# Backlit-PCB-Art-Lamp.net
KiCad netlist of a schematic drawn in EasyEDA Pro
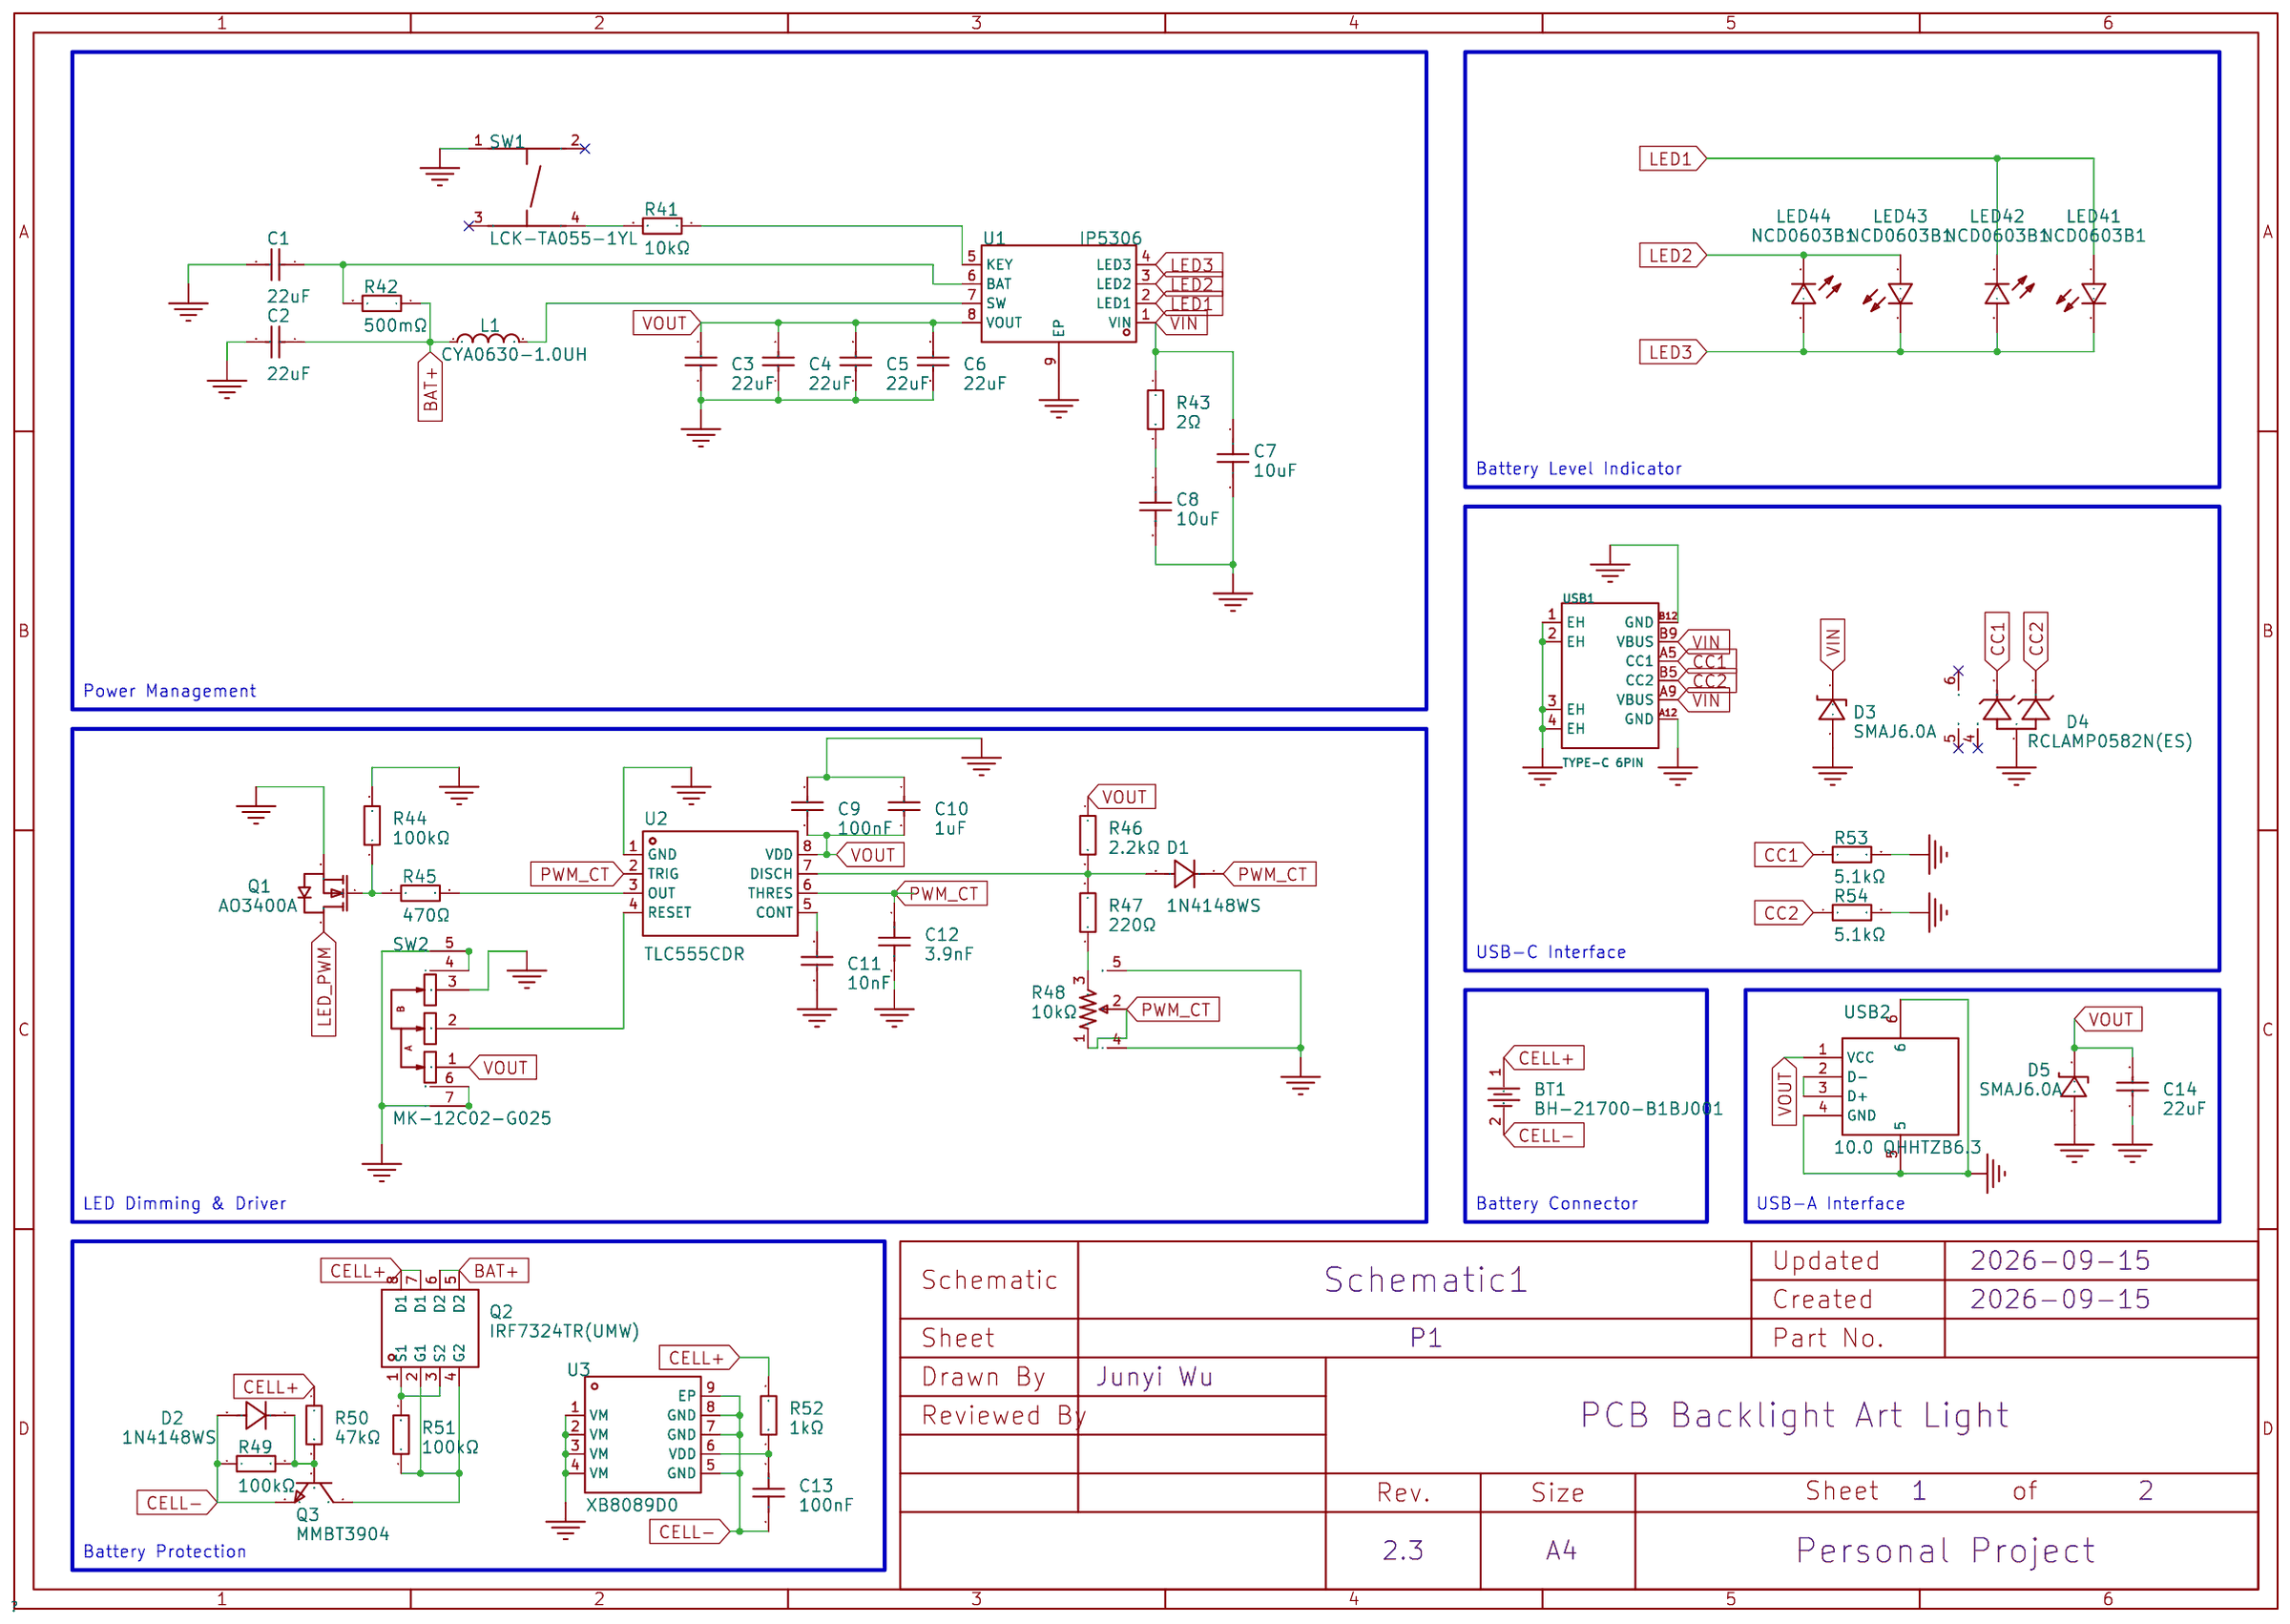
[diagram p0: Power & Control]
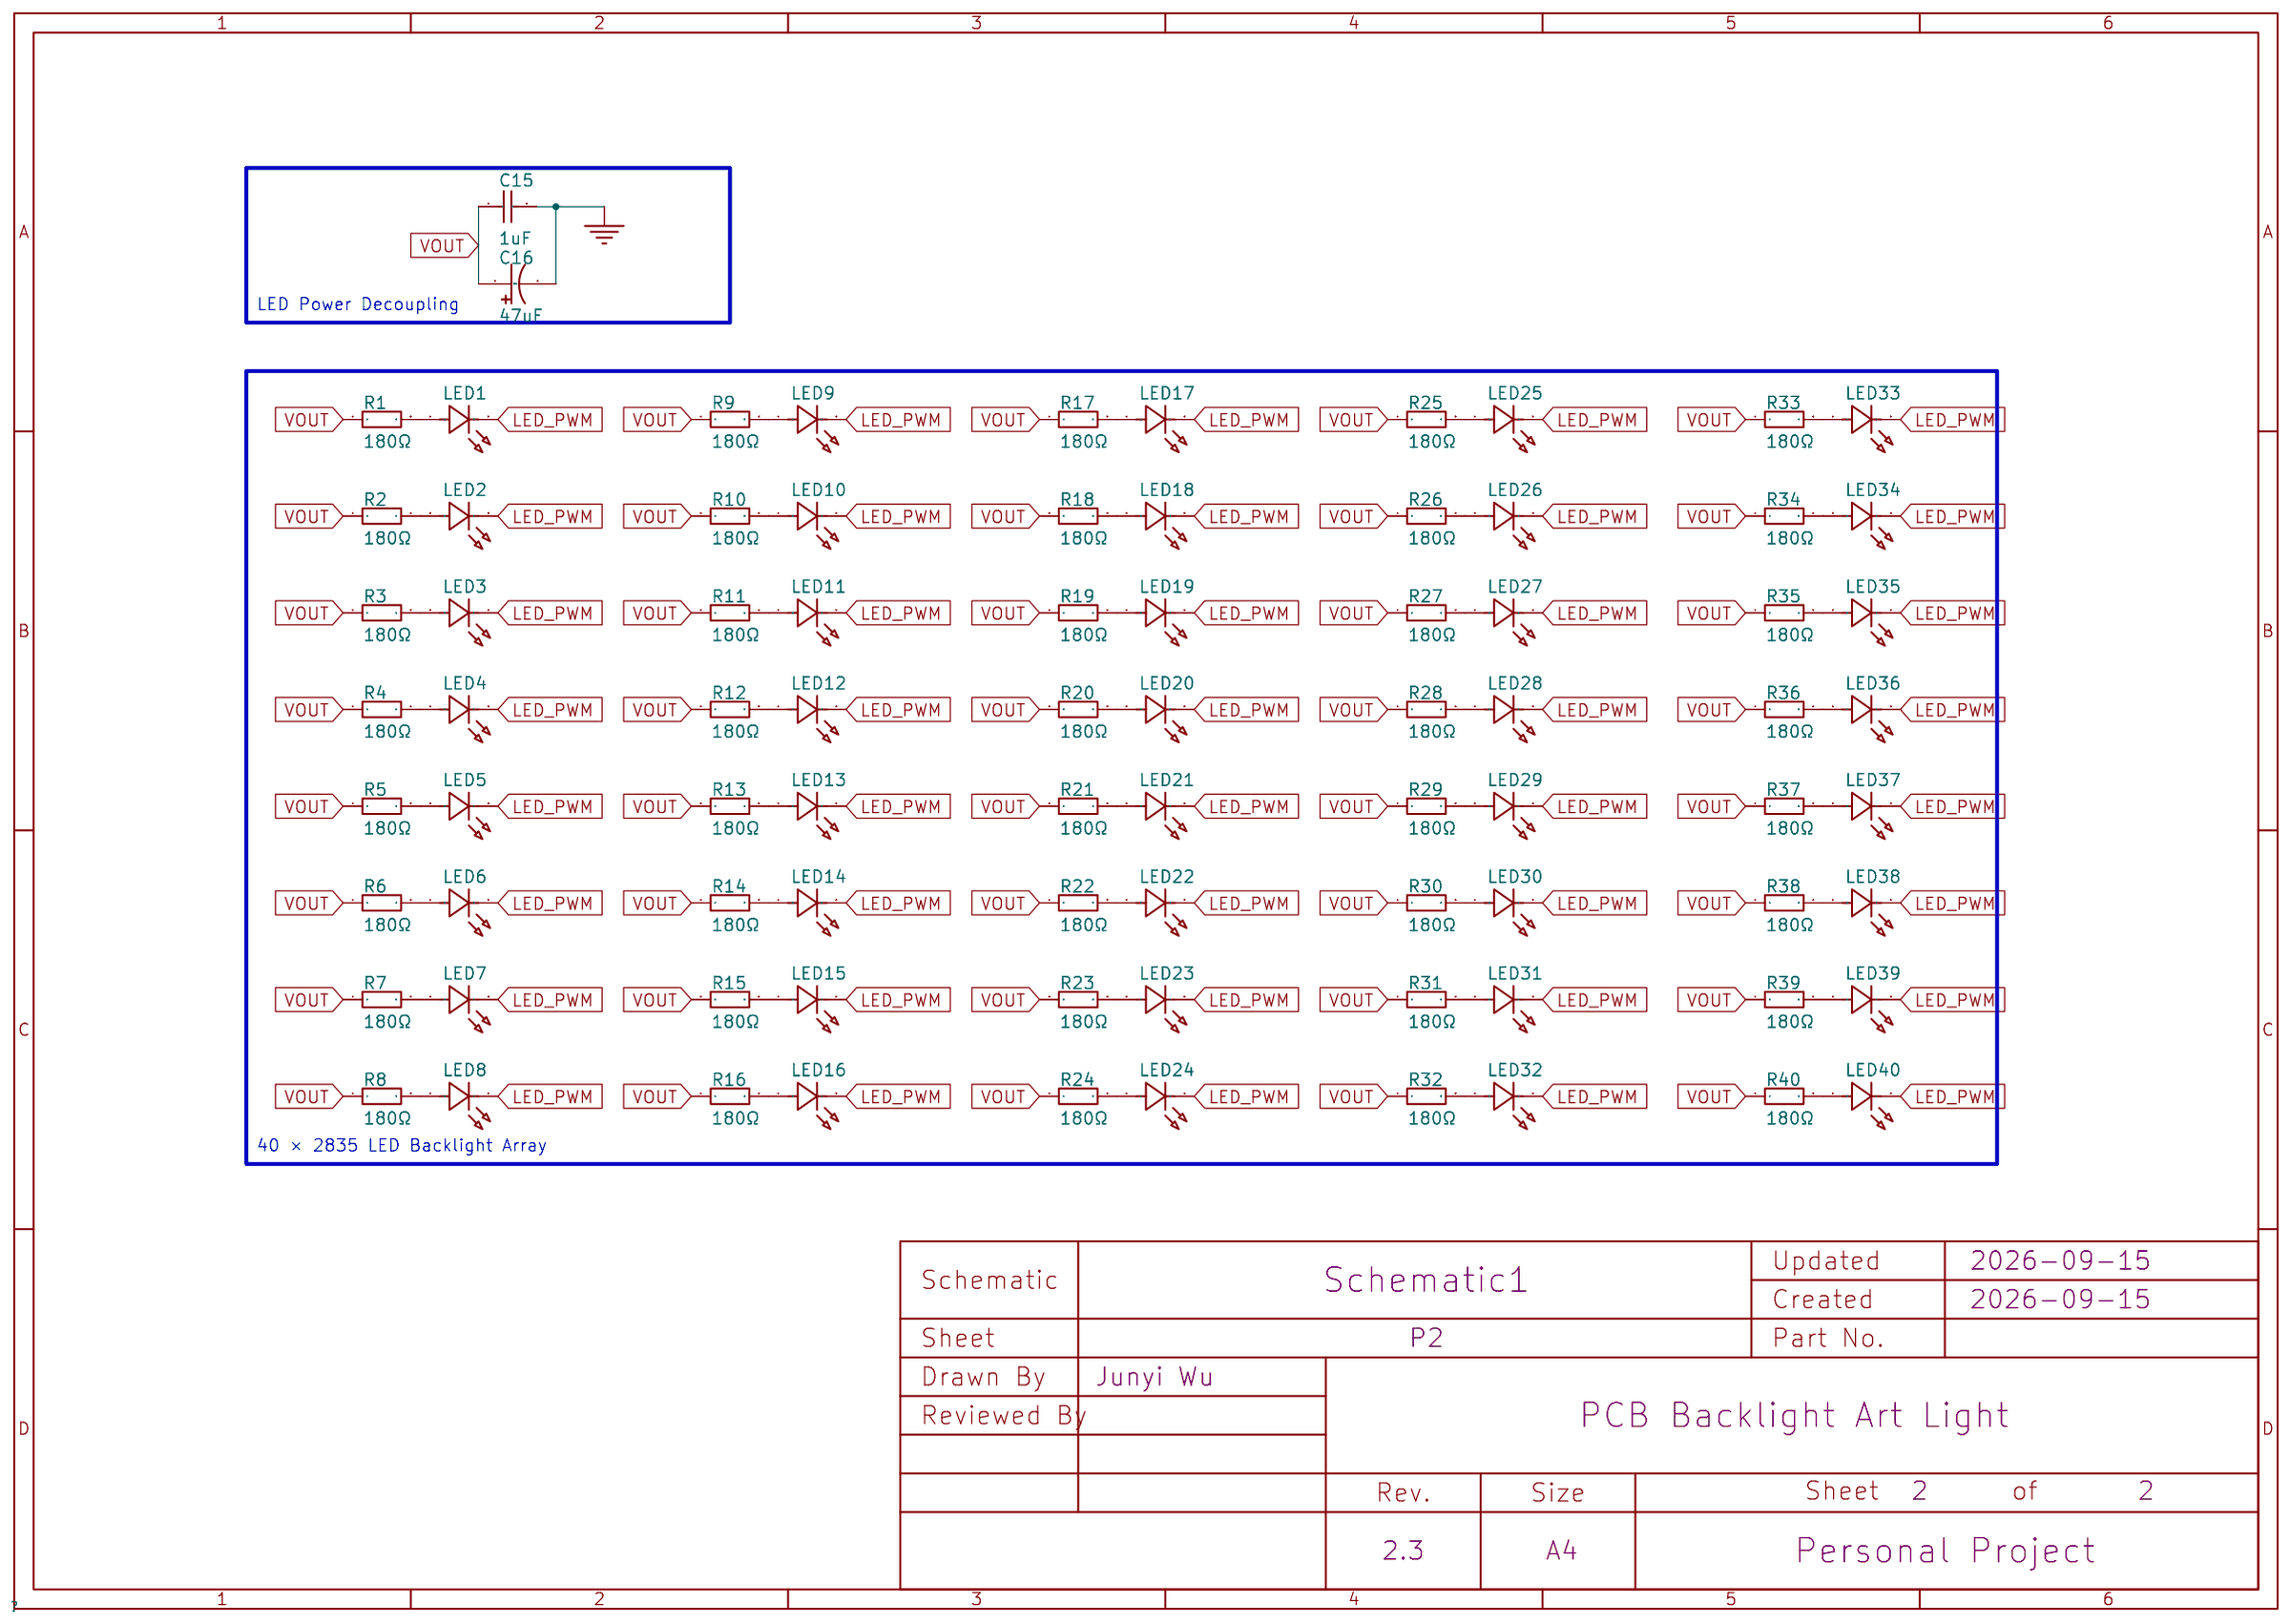
[diagram p1: LED Array]

(export (version "E")
  (design (tool "Eeschema 10.0.6"))
  (components
    (comp (ref "BT1")
      (value "BH-21700-B1BJ001")
      (fields (field (name "Manufacturer") "MYOUNG(美阳)"))
      (libsource (lib "easyedapro") (part "BH-21700-B1BJ001_1"))
    )
    (comp (ref "C1")
      (value "22uF")
      (footprint "easyedapro:C1206")
      (description "容值:22uF;精度:±10%;额定电压:25V;温度系数:X5R;")
      (fields
        (field (name "Manufacturer Part") "CL31A226KAHNNNE")
        (field (name "Manufacturer") "SAMSUNG(三星)")
      )
      (libsource (lib "easyedapro") (part "CL31A226KAHNNNE"))
    )
    (comp (ref "C2")
      (value "22uF")
      (footprint "easyedapro:C1206")
      (description "容值:22uF;精度:±10%;额定电压:25V;温度系数:X5R;")
      (fields
        (field (name "Manufacturer Part") "CL31A226KAHNNNE")
        (field (name "Manufacturer") "SAMSUNG(三星)")
      )
      (libsource (lib "easyedapro") (part "CL31A226KAHNNNE"))
    )
    (comp (ref "C3")
      (value "22uF")
      (footprint "easyedapro:C1206")
      (description "容值:22uF;精度:±10%;额定电压:25V;温度系数:X5R;")
      (fields
        (field (name "Manufacturer Part") "CL31A226KAHNNNE")
        (field (name "Manufacturer") "SAMSUNG(三星)")
      )
      (libsource (lib "easyedapro") (part "CL31A226KAHNNNE"))
    )
    (comp (ref "C4")
      (value "22uF")
      (footprint "easyedapro:C1206")
      (description "容值:22uF;精度:±10%;额定电压:25V;温度系数:X5R;")
      (fields
        (field (name "Manufacturer Part") "CL31A226KAHNNNE")
        (field (name "Manufacturer") "SAMSUNG(三星)")
      )
      (libsource (lib "easyedapro") (part "CL31A226KAHNNNE"))
    )
    (comp (ref "C5")
      (value "22uF")
      (footprint "easyedapro:C1206")
      (description "容值:22uF;精度:±10%;额定电压:25V;温度系数:X5R;")
      (fields
        (field (name "Manufacturer Part") "CL31A226KAHNNNE")
        (field (name "Manufacturer") "SAMSUNG(三星)")
      )
      (libsource (lib "easyedapro") (part "CL31A226KAHNNNE"))
    )
    (comp (ref "C6")
      (value "22uF")
      (footprint "easyedapro:C1206")
      (description "容值:22uF;精度:±10%;额定电压:25V;温度系数:X5R;")
      (fields
        (field (name "Manufacturer Part") "CL31A226KAHNNNE")
        (field (name "Manufacturer") "SAMSUNG(三星)")
      )
      (libsource (lib "easyedapro") (part "CL31A226KAHNNNE"))
    )
    (comp (ref "C7")
      (value "10uF")
      (footprint "easyedapro:C0603")
      (fields
        (field (name "Manufacturer Part") "CL10A106MA8NRNC")
        (field (name "Manufacturer") "SAMSUNG(三星)")
      )
      (libsource (lib "easyedapro") (part "CL10A106MA8NRNC"))
    )
    (comp (ref "C8")
      (value "10uF")
      (footprint "easyedapro:C0603")
      (fields
        (field (name "Manufacturer Part") "CL10A106MA8NRNC")
        (field (name "Manufacturer") "SAMSUNG(三星)")
      )
      (libsource (lib "easyedapro") (part "CL10A106MA8NRNC"))
    )
    (comp (ref "C9")
      (value "100nF")
      (footprint "easyedapro:C0603")
      (description "容值:100nF;精度:±10%;额定电压:16V;温度系数:X7R;")
      (fields
        (field (name "Manufacturer Part") "CL10B104KO8NNNC")
        (field (name "Manufacturer") "SAMSUNG(三星)")
      )
      (libsource (lib "easyedapro") (part "CL10B104KO8NNNC"))
    )
    (comp (ref "C10")
      (value "1uF")
      (footprint "easyedapro:C0603")
      (fields
        (field (name "Manufacturer Part") "CC0603KRX5R8BB105")
        (field (name "Manufacturer") "YAGEO(国巨)")
      )
      (libsource (lib "easyedapro") (part "CC0603KRX5R8BB105"))
    )
    (comp (ref "C11")
      (value "10nF")
      (footprint "easyedapro:C0603")
      (fields
        (field (name "Manufacturer Part") "CC0603JRX7R9BB103")
        (field (name "Manufacturer") "YAGEO(国巨)")
      )
      (libsource (lib "easyedapro") (part "CC0603JRX7R9BB103"))
    )
    (comp (ref "C12")
      (value "3.9nF")
      (footprint "easyedapro:C0603")
      (fields
        (field (name "Manufacturer Part") "GRM1885C1H392JA01D")
        (field (name "Manufacturer") "muRata(村田)")
      )
      (libsource (lib "easyedapro") (part "GRM1885C1H392JA01D"))
    )
    (comp (ref "C13")
      (value "100nF")
      (footprint "easyedapro:C0603")
      (description "容值:100nF;精度:±10%;额定电压:50V;温度系数:X7R;")
      (fields
        (field (name "Manufacturer Part") "CC0603KRX7R9BB104")
        (field (name "Manufacturer") "YAGEO(国巨)")
      )
      (libsource (lib "easyedapro") (part "CC0603KRX7R9BB104"))
    )
    (comp (ref "C14")
      (value "22uF")
      (footprint "easyedapro:C1206")
      (description "容值:22uF;精度:±10%;额定电压:25V;温度系数:X5R;")
      (fields
        (field (name "Manufacturer Part") "CL31A226KAHNNNE")
        (field (name "Manufacturer") "SAMSUNG(三星)")
      )
      (libsource (lib "easyedapro") (part "CL31A226KAHNNNE"))
    )
    (comp (ref "D1")
      (value "1N4148WS")
      (footprint "easyedapro:SOD-323_L1.8-W1.3-LS2.5-RD")
      (fields (field (name "Manufacturer") "JSMSEMI(杰盛微)"))
      (libsource (lib "easyedapro") (part "1N4148WS_C917117"))
    )
    (comp (ref "D2")
      (value "1N4148WS")
      (footprint "easyedapro:SOD-323_L1.8-W1.3-LS2.5-RD")
      (description "二极管配置:独立式;整流电流:200mA;直流反向耐压(Vr):75V;正向压降(Vf):1.25V@150mA;反向恢复时间(Trr):4ns;")
      (fields (field (name "Manufacturer") "JSMSEMI(杰盛微)"))
      (libsource (lib "easyedapro") (part "1N4148WS_C917117"))
    )
    (comp (ref "D3")
      (value "SMAJ6.0A")
      (footprint "easyedapro:SMA_L4.3-W2.6-LS5.1-RD")
      (fields (field (name "Manufacturer") "MDD(辰达半导体)"))
      (libsource (lib "easyedapro") (part "SMAJ6.0A_C364284"))
    )
    (comp (ref "D4")
      (value "RCLAMP0582N(ES)")
      (footprint "easyedapro:DFN1210-6_L1.2-W1.0-P0.40-BL")
      (fields (field (name "Manufacturer") "ElecSuper(静芯)"))
      (libsource (lib "easyedapro") (part "RCLAMP0582N(ES)"))
    )
    (comp (ref "D5")
      (value "SMAJ6.0A")
      (footprint "easyedapro:SMA_L4.3-W2.6-LS5.1-RD")
      (description "极性:单向;反向截止电压(Vrwm):6V;钳位电压:10.3V;峰值脉冲电流(Ipp):38.8A;峰值脉冲功率(Ppp):400W@10/1000us;击穿电压(VBR):7.37V;")
      (fields (field (name "Manufacturer") "MDD(辰达半导体)"))
      (libsource (lib "easyedapro") (part "SMAJ6.0A_C364284"))
    )
    (comp (ref "L1")
      (value "CYA0630-1.0UH")
      (footprint "easyedapro:IND-SMD_L7.2-W6.6_GPSR0730")
      (fields (field (name "Manufacturer") "SHOU HAN(首韩)"))
      (libsource (lib "easyedapro") (part "CYA0630-1.0UH"))
    )
    (comp (ref "LED41")
      (value "NCD0603B1")
      (footprint "easyedapro:LED0603-RD")
      (fields (field (name "Manufacturer") "国星光电"))
      (libsource (lib "easyedapro") (part "FC-DA1608BK-470H10"))
    )
    (comp (ref "LED42")
      (value "NCD0603B1")
      (footprint "easyedapro:LED0603-RD")
      (fields (field (name "Manufacturer") "国星光电"))
      (libsource (lib "easyedapro") (part "FC-DA1608BK-470H10"))
    )
    (comp (ref "LED43")
      (value "NCD0603B1")
      (footprint "easyedapro:LED0603-RD")
      (fields (field (name "Manufacturer") "国星光电"))
      (libsource (lib "easyedapro") (part "FC-DA1608BK-470H10"))
    )
    (comp (ref "LED44")
      (value "NCD0603B1")
      (footprint "easyedapro:LED0603-RD")
      (fields (field (name "Manufacturer") "国星光电"))
      (libsource (lib "easyedapro") (part "FC-DA1608BK-470H10"))
    )
    (comp (ref "Q1")
      (value "AO3400A")
      (footprint "easyedapro:SOT-23-3_L2.9-W1.3-P1.90-LS2.4-BR")
      (fields (field (name "Manufacturer") "UMW(友台半导体)"))
      (libsource (lib "easyedapro") (part "AO3400A_C347475"))
    )
    (comp (ref "Q2")
      (value "IRF7324TR(UMW)")
      (footprint "easyedapro:SOP-8_L4.9-W3.9-P1.27-LS6.0-BL")
      (fields (field (name "Manufacturer") "UMW(友台半导体)"))
      (libsource (lib "easyedapro") (part "IRF7324TR(UMW)"))
    )
    (comp (ref "Q3")
      (value "MMBT3904")
      (footprint "easyedapro:SOT-23-3_L2.9-W1.3-P1.90-LS2.4-BR")
      (fields (field (name "Manufacturer") "R+O(宏嘉诚)"))
      (libsource (lib "easyedapro") (part "MMBT3904_C7420353"))
    )
    (comp (ref "R41")
      (value "10kΩ")
      (footprint "easyedapro:R0603")
      (description "电阻类型:厚膜电阻;阻值:10kΩ;精度:±1%;功率:100mW;工作电压:75V;温度系数:±100ppm/℃;")
      (fields
        (field (name "Manufacturer Part") "0603WAF1002T5E")
        (field (name "Manufacturer") "UNI-ROYAL(厚声)")
      )
      (libsource (lib "easyedapro") (part "0603WAF1002T5E"))
    )
    (comp (ref "R42")
      (value "500mΩ")
      (footprint "easyedapro:R0603")
      (fields
        (field (name "Manufacturer Part") "0603WAF500LT5E")
        (field (name "Manufacturer") "UNI-ROYAL(厚声)")
      )
      (libsource (lib "easyedapro") (part "0603WAF500LT5E"))
    )
    (comp (ref "R43")
      (value "2Ω")
      (footprint "easyedapro:R0603")
      (fields
        (field (name "Manufacturer Part") "0603WAF200KT5E")
        (field (name "Manufacturer") "UNI-ROYAL(厚声)")
      )
      (libsource (lib "easyedapro") (part "0603WAF200KT5E"))
    )
    (comp (ref "R44")
      (value "100kΩ")
      (footprint "easyedapro:R0603")
      (fields
        (field (name "Manufacturer Part") "0603WAF1003T5E")
        (field (name "Manufacturer") "UNI-ROYAL(厚声)")
      )
      (libsource (lib "easyedapro") (part "0603WAF1003T5E"))
    )
    (comp (ref "R45")
      (value "470Ω")
      (footprint "easyedapro:R0603")
      (fields
        (field (name "Manufacturer Part") "0603WAF4700T5E")
        (field (name "Manufacturer") "UNI-ROYAL(厚声)")
      )
      (libsource (lib "easyedapro") (part "0603WAF4700T5E"))
    )
    (comp (ref "R46")
      (value "2.2kΩ")
      (footprint "easyedapro:R0603")
      (fields
        (field (name "Manufacturer Part") "0603WAF2201T5E")
        (field (name "Manufacturer") "UNI-ROYAL(厚声)")
      )
      (libsource (lib "easyedapro") (part "0603WAF2201T5E"))
    )
    (comp (ref "R47")
      (value "220Ω")
      (footprint "easyedapro:R0603")
      (fields
        (field (name "Manufacturer Part") "0603WAF2200T5E")
        (field (name "Manufacturer") "UNI-ROYAL(厚声)")
      )
      (libsource (lib "easyedapro") (part "0603WAF2200T5E"))
    )
    (comp (ref "R48")
      (value "10kΩ")
      (footprint "easyedapro:3脚拨盘电位器")
      (fields
        (field (name "Manufacturer Part") "B103")
        (field (name "Manufacturer") "RISYM(维芯)")
        (field (name "Tolerance") "±20%")
      )
      (libsource (lib "easyedapro") (part "3脚拨盘电位器"))
    )
    (comp (ref "R49")
      (value "100kΩ")
      (footprint "easyedapro:R0603")
      (description "电阻类型:厚膜电阻;阻值:100kΩ;精度:±1%;功率:100mW;工作电压:75V;温度系数:±100ppm/℃;")
      (fields
        (field (name "Manufacturer Part") "0603WAF1003T5E")
        (field (name "Manufacturer") "UNI-ROYAL(厚声)")
      )
      (libsource (lib "easyedapro") (part "0603WAF1003T5E"))
    )
    (comp (ref "R50")
      (value "47kΩ")
      (footprint "easyedapro:R0603")
      (fields
        (field (name "Manufacturer Part") "0603WAF4702T5E")
        (field (name "Manufacturer") "UNI-ROYAL(厚声)")
      )
      (libsource (lib "easyedapro") (part "0603WAF4702T5E"))
    )
    (comp (ref "R51")
      (value "100kΩ")
      (footprint "easyedapro:R0603")
      (description "电阻类型:厚膜电阻;阻值:100kΩ;精度:±1%;功率:100mW;工作电压:75V;温度系数:±100ppm/℃;")
      (fields
        (field (name "Manufacturer Part") "0603WAF1003T5E")
        (field (name "Manufacturer") "UNI-ROYAL(厚声)")
      )
      (libsource (lib "easyedapro") (part "0603WAF1003T5E"))
    )
    (comp (ref "R52")
      (value "1kΩ")
      (footprint "easyedapro:R0603")
      (fields
        (field (name "Manufacturer Part") "0603WAF1001T5E")
        (field (name "Manufacturer") "UNI-ROYAL(厚声)")
      )
      (libsource (lib "easyedapro") (part "0603WAF1001T5E"))
    )
    (comp (ref "R53")
      (value "5.1kΩ")
      (footprint "easyedapro:R0603")
      (description "电阻类型:厚膜电阻;阻值:5.1kΩ;精度:±1%;功率:100mW;工作电压:75V;温度系数:±100ppm/℃;")
      (fields
        (field (name "Manufacturer Part") "0603WAF5101T5E")
        (field (name "Manufacturer") "UNI-ROYAL(厚声)")
      )
      (libsource (lib "easyedapro") (part "0603WAF5101T5E"))
    )
    (comp (ref "R54")
      (value "5.1kΩ")
      (footprint "easyedapro:R0603")
      (description "电阻类型:厚膜电阻;阻值:5.1kΩ;精度:±1%;功率:100mW;工作电压:75V;温度系数:±100ppm/℃;")
      (fields
        (field (name "Manufacturer Part") "0603WAF5101T5E")
        (field (name "Manufacturer") "UNI-ROYAL(厚声)")
      )
      (libsource (lib "easyedapro") (part "0603WAF5101T5E"))
    )
    (comp (ref "SW1")
      (value "LCK-TA055-1YL")
      (footprint "easyedapro:KEY-SMD_4P-L4.7-W3.6_LCK-TA055-1YL")
      (fields (field (name "Manufacturer") "LCKELEC(联晟欣)"))
      (libsource (lib "easyedapro") (part "LCK-TA055-1YL"))
    )
    (comp (ref "SW2")
      (value "MK-12C02-G025")
      (footprint "easyedapro:SW-SMD_MK-12C02-G025")
      (fields (field (name "Manufacturer") "G-Switch(品赞)"))
      (libsource (lib "easyedapro") (part "MK-12C02-G025"))
    )
    (comp (ref "U1")
      (value "IP5306")
      (footprint "easyedapro:ESOP-8_L4.9-W3.9-P1.27-LS6.0-BL-EP")
      (description "工作电压:4.65V~5.5V;最大充电电流:2.1A;电池类型:锂电池;电池节数:1;")
      (fields (field (name "Manufacturer") "INJOINIC(英集芯)"))
      (libsource (lib "easyedapro") (part "IP5306"))
    )
    (comp (ref "U2")
      (value "TLC555CDR")
      (footprint "easyedapro:SOIC-8_L5.0-W4.0-P1.27-LS6.0-BL")
      (fields (field (name "Manufacturer") "TI(德州仪器)"))
      (libsource (lib "easyedapro") (part "TLC555CDR"))
    )
    (comp (ref "U3")
      (value "XB8089D0")
      (footprint "easyedapro:SOIC-8_L4.9-W3.9-P1.27-LS6.0-BL-EP3.3-1")
      (fields (field (name "Manufacturer") "xysemi(赛芯微)"))
      (libsource (lib "easyedapro") (part "XB8089D0"))
    )
    (comp (ref "USB1")
      (value "TYPE-C 6PIN")
      (footprint "easyedapro:USB-SMD_TYPE-C-6PIN")
      (description "连接器类型:Type-C;协议标准:USB 3.1;公母:母;安装方式:卧贴;触点数量:6P;端口数量:1;额定电流 - 电源:3A;工作温度:-25℃~+85℃;")
      (fields (field (name "Manufacturer") "SHOU HAN(首韩)"))
      (libsource (lib "easyedapro") (part "TYPE-C 6PIN"))
    )
    (comp (ref "USB2")
      (value "10.0 QHHTZB6.3")
      (footprint "easyedapro:USB-A-TH_10.0QHHTZB6.3")
      (fields (field (name "Manufacturer") "SHOU HAN(首韩)"))
      (libsource (lib "easyedapro") (part "10.0 QHHTZB6.3"))
    )
    (comp (ref "C15")
      (value "1uF")
      (footprint "easyedapro:C0603")
      (fields
        (field (name "Manufacturer Part") "CC0603KRX5R8BB105")
        (field (name "Manufacturer") "YAGEO(国巨)")
      )
      (libsource (lib "easyedapro") (part "CC0603KRX5R8BB105"))
    )
    (comp (ref "C16")
      (value "47uF")
      (footprint "easyedapro:CAP-SMD_BD5.0-L5.3-W5.3-LS6.5-FD-1")
      (fields (field (name "Manufacturer Part") "EEEFK1C470UR") (field (name "Manufacturer") "PANASONIC(松下)"))
      (libsource (lib "easyedapro") (part "EEEFK1C470UR"))
    )
    (comp (ref "LED1")
      (value "~")
      (footprint "easyedapro:RCW 2835 LED")
      (fields (field (name "Manufacturer") "RCW"))
      (libsource (lib "easyedapro") (part "RCW 2835 LED"))
    )
    (comp (ref "LED2")
      (value "~")
      (footprint "easyedapro:RCW 2835 LED")
      (fields (field (name "Manufacturer") "RCW"))
      (libsource (lib "easyedapro") (part "RCW 2835 LED"))
    )
    (comp (ref "LED3")
      (value "~")
      (footprint "easyedapro:RCW 2835 LED")
      (fields (field (name "Manufacturer") "RCW"))
      (libsource (lib "easyedapro") (part "RCW 2835 LED"))
    )
    (comp (ref "LED4")
      (value "~")
      (footprint "easyedapro:RCW 2835 LED")
      (fields (field (name "Manufacturer") "RCW"))
      (libsource (lib "easyedapro") (part "RCW 2835 LED"))
    )
    (comp (ref "LED5")
      (value "~")
      (footprint "easyedapro:RCW 2835 LED")
      (fields (field (name "Manufacturer") "RCW"))
      (libsource (lib "easyedapro") (part "RCW 2835 LED"))
    )
    (comp (ref "LED6")
      (value "~")
      (footprint "easyedapro:RCW 2835 LED")
      (fields (field (name "Manufacturer") "RCW"))
      (libsource (lib "easyedapro") (part "RCW 2835 LED"))
    )
    (comp (ref "LED7")
      (value "~")
      (footprint "easyedapro:RCW 2835 LED")
      (fields (field (name "Manufacturer") "RCW"))
      (libsource (lib "easyedapro") (part "RCW 2835 LED"))
    )
    (comp (ref "LED8")
      (value "~")
      (footprint "easyedapro:RCW 2835 LED")
      (fields (field (name "Manufacturer") "RCW"))
      (libsource (lib "easyedapro") (part "RCW 2835 LED"))
    )
    (comp (ref "LED9")
      (value "~")
      (footprint "easyedapro:RCW 2835 LED")
      (fields (field (name "Manufacturer") "RCW"))
      (libsource (lib "easyedapro") (part "RCW 2835 LED"))
    )
    (comp (ref "LED10")
      (value "~")
      (footprint "easyedapro:RCW 2835 LED")
      (fields (field (name "Manufacturer") "RCW"))
      (libsource (lib "easyedapro") (part "RCW 2835 LED"))
    )
    (comp (ref "LED11")
      (value "~")
      (footprint "easyedapro:RCW 2835 LED")
      (fields (field (name "Manufacturer") "RCW"))
      (libsource (lib "easyedapro") (part "RCW 2835 LED"))
    )
    (comp (ref "LED12")
      (value "~")
      (footprint "easyedapro:RCW 2835 LED")
      (fields (field (name "Manufacturer") "RCW"))
      (libsource (lib "easyedapro") (part "RCW 2835 LED"))
    )
    (comp (ref "LED13")
      (value "~")
      (footprint "easyedapro:RCW 2835 LED")
      (fields (field (name "Manufacturer") "RCW"))
      (libsource (lib "easyedapro") (part "RCW 2835 LED"))
    )
    (comp (ref "LED14")
      (value "~")
      (footprint "easyedapro:RCW 2835 LED")
      (fields (field (name "Manufacturer") "RCW"))
      (libsource (lib "easyedapro") (part "RCW 2835 LED"))
    )
    (comp (ref "LED15")
      (value "~")
      (footprint "easyedapro:RCW 2835 LED")
      (fields (field (name "Manufacturer") "RCW"))
      (libsource (lib "easyedapro") (part "RCW 2835 LED"))
    )
    (comp (ref "LED16")
      (value "~")
      (footprint "easyedapro:RCW 2835 LED")
      (fields (field (name "Manufacturer") "RCW"))
      (libsource (lib "easyedapro") (part "RCW 2835 LED"))
    )
    (comp (ref "LED17")
      (value "~")
      (footprint "easyedapro:RCW 2835 LED")
      (fields (field (name "Manufacturer") "RCW"))
      (libsource (lib "easyedapro") (part "RCW 2835 LED"))
    )
    (comp (ref "LED18")
      (value "~")
      (footprint "easyedapro:RCW 2835 LED")
      (fields (field (name "Manufacturer") "RCW"))
      (libsource (lib "easyedapro") (part "RCW 2835 LED"))
    )
    (comp (ref "LED19")
      (value "~")
      (footprint "easyedapro:RCW 2835 LED")
      (fields (field (name "Manufacturer") "RCW"))
      (libsource (lib "easyedapro") (part "RCW 2835 LED"))
    )
    (comp (ref "LED20")
      (value "~")
      (footprint "easyedapro:RCW 2835 LED")
      (fields (field (name "Manufacturer") "RCW"))
      (libsource (lib "easyedapro") (part "RCW 2835 LED"))
    )
    (comp (ref "LED21")
      (value "~")
      (footprint "easyedapro:RCW 2835 LED")
      (fields (field (name "Manufacturer") "RCW"))
      (libsource (lib "easyedapro") (part "RCW 2835 LED"))
    )
    (comp (ref "LED22")
      (value "~")
      (footprint "easyedapro:RCW 2835 LED")
      (fields (field (name "Manufacturer") "RCW"))
      (libsource (lib "easyedapro") (part "RCW 2835 LED"))
    )
    (comp (ref "LED23")
      (value "~")
      (footprint "easyedapro:RCW 2835 LED")
      (fields (field (name "Manufacturer") "RCW"))
      (libsource (lib "easyedapro") (part "RCW 2835 LED"))
    )
    (comp (ref "LED24")
      (value "~")
      (footprint "easyedapro:RCW 2835 LED")
      (fields (field (name "Manufacturer") "RCW"))
      (libsource (lib "easyedapro") (part "RCW 2835 LED"))
    )
    (comp (ref "LED25")
      (value "~")
      (footprint "easyedapro:RCW 2835 LED")
      (fields (field (name "Manufacturer") "RCW"))
      (libsource (lib "easyedapro") (part "RCW 2835 LED"))
    )
    (comp (ref "LED26")
      (value "~")
      (footprint "easyedapro:RCW 2835 LED")
      (fields (field (name "Manufacturer") "RCW"))
      (libsource (lib "easyedapro") (part "RCW 2835 LED"))
    )
    (comp (ref "LED27")
      (value "~")
      (footprint "easyedapro:RCW 2835 LED")
      (fields (field (name "Manufacturer") "RCW"))
      (libsource (lib "easyedapro") (part "RCW 2835 LED"))
    )
    (comp (ref "LED28")
      (value "~")
      (footprint "easyedapro:RCW 2835 LED")
      (fields (field (name "Manufacturer") "RCW"))
      (libsource (lib "easyedapro") (part "RCW 2835 LED"))
    )
    (comp (ref "LED29")
      (value "~")
      (footprint "easyedapro:RCW 2835 LED")
      (fields (field (name "Manufacturer") "RCW"))
      (libsource (lib "easyedapro") (part "RCW 2835 LED"))
    )
    (comp (ref "LED30")
      (value "~")
      (footprint "easyedapro:RCW 2835 LED")
      (fields (field (name "Manufacturer") "RCW"))
      (libsource (lib "easyedapro") (part "RCW 2835 LED"))
    )
    (comp (ref "LED31")
      (value "~")
      (footprint "easyedapro:RCW 2835 LED")
      (fields (field (name "Manufacturer") "RCW"))
      (libsource (lib "easyedapro") (part "RCW 2835 LED"))
    )
    (comp (ref "LED32")
      (value "~")
      (footprint "easyedapro:RCW 2835 LED")
      (fields (field (name "Manufacturer") "RCW"))
      (libsource (lib "easyedapro") (part "RCW 2835 LED"))
    )
    (comp (ref "LED33")
      (value "~")
      (footprint "easyedapro:RCW 2835 LED")
      (fields (field (name "Manufacturer") "RCW"))
      (libsource (lib "easyedapro") (part "RCW 2835 LED"))
    )
    (comp (ref "LED34")
      (value "~")
      (footprint "easyedapro:RCW 2835 LED")
      (fields (field (name "Manufacturer") "RCW"))
      (libsource (lib "easyedapro") (part "RCW 2835 LED"))
    )
    (comp (ref "LED35")
      (value "~")
      (footprint "easyedapro:RCW 2835 LED")
      (fields (field (name "Manufacturer") "RCW"))
      (libsource (lib "easyedapro") (part "RCW 2835 LED"))
    )
    (comp (ref "LED36")
      (value "~")
      (footprint "easyedapro:RCW 2835 LED")
      (fields (field (name "Manufacturer") "RCW"))
      (libsource (lib "easyedapro") (part "RCW 2835 LED"))
    )
    (comp (ref "LED37")
      (value "~")
      (footprint "easyedapro:RCW 2835 LED")
      (fields (field (name "Manufacturer") "RCW"))
      (libsource (lib "easyedapro") (part "RCW 2835 LED"))
    )
    (comp (ref "LED38")
      (value "~")
      (footprint "easyedapro:RCW 2835 LED")
      (fields (field (name "Manufacturer") "RCW"))
      (libsource (lib "easyedapro") (part "RCW 2835 LED"))
    )
    (comp (ref "LED39")
      (value "~")
      (footprint "easyedapro:RCW 2835 LED")
      (fields (field (name "Manufacturer") "RCW"))
      (libsource (lib "easyedapro") (part "RCW 2835 LED"))
    )
    (comp (ref "LED40")
      (value "~")
      (footprint "easyedapro:RCW 2835 LED")
      (fields (field (name "Manufacturer") "RCW"))
      (libsource (lib "easyedapro") (part "RCW 2835 LED"))
    )
    (comp (ref "R1")
      (value "180Ω")
      (footprint "easyedapro:R0603")
      (description "电阻类型:厚膜电阻;阻值:180Ω;精度:±1%;功率:100mW;最大工作电压:75V;温度系数:±100ppm/℃;")
      (fields
        (field (name "Manufacturer Part") "0603WAF1800T5E")
        (field (name "Manufacturer") "UNI-ROYAL(厚声)")
      )
      (libsource (lib "easyedapro") (part "0603WAF1800T5E"))
    )
    (comp (ref "R2")
      (value "180Ω")
      (footprint "easyedapro:R0603")
      (description "电阻类型:厚膜电阻;阻值:180Ω;精度:±1%;功率:100mW;最大工作电压:75V;温度系数:±100ppm/℃;")
      (fields
        (field (name "Manufacturer Part") "0603WAF1800T5E")
        (field (name "Manufacturer") "UNI-ROYAL(厚声)")
      )
      (libsource (lib "easyedapro") (part "0603WAF1800T5E"))
    )
    (comp (ref "R3")
      (value "180Ω")
      (footprint "easyedapro:R0603")
      (description "电阻类型:厚膜电阻;阻值:180Ω;精度:±1%;功率:100mW;最大工作电压:75V;温度系数:±100ppm/℃;")
      (fields
        (field (name "Manufacturer Part") "0603WAF1800T5E")
        (field (name "Manufacturer") "UNI-ROYAL(厚声)")
      )
      (libsource (lib "easyedapro") (part "0603WAF1800T5E"))
    )
    (comp (ref "R4")
      (value "180Ω")
      (footprint "easyedapro:R0603")
      (description "电阻类型:厚膜电阻;阻值:180Ω;精度:±1%;功率:100mW;最大工作电压:75V;温度系数:±100ppm/℃;")
      (fields
        (field (name "Manufacturer Part") "0603WAF1800T5E")
        (field (name "Manufacturer") "UNI-ROYAL(厚声)")
      )
      (libsource (lib "easyedapro") (part "0603WAF1800T5E"))
    )
    (comp (ref "R5")
      (value "180Ω")
      (footprint "easyedapro:R0603")
      (description "电阻类型:厚膜电阻;阻值:180Ω;精度:±1%;功率:100mW;最大工作电压:75V;温度系数:±100ppm/℃;")
      (fields
        (field (name "Manufacturer Part") "0603WAF1800T5E")
        (field (name "Manufacturer") "UNI-ROYAL(厚声)")
      )
      (libsource (lib "easyedapro") (part "0603WAF1800T5E"))
    )
    (comp (ref "R6")
      (value "180Ω")
      (footprint "easyedapro:R0603")
      (description "电阻类型:厚膜电阻;阻值:180Ω;精度:±1%;功率:100mW;最大工作电压:75V;温度系数:±100ppm/℃;")
      (fields
        (field (name "Manufacturer Part") "0603WAF1800T5E")
        (field (name "Manufacturer") "UNI-ROYAL(厚声)")
      )
      (libsource (lib "easyedapro") (part "0603WAF1800T5E"))
    )
    (comp (ref "R7")
      (value "180Ω")
      (footprint "easyedapro:R0603")
      (description "电阻类型:厚膜电阻;阻值:180Ω;精度:±1%;功率:100mW;最大工作电压:75V;温度系数:±100ppm/℃;")
      (fields
        (field (name "Manufacturer Part") "0603WAF1800T5E")
        (field (name "Manufacturer") "UNI-ROYAL(厚声)")
      )
      (libsource (lib "easyedapro") (part "0603WAF1800T5E"))
    )
    (comp (ref "R8")
      (value "180Ω")
      (footprint "easyedapro:R0603")
      (description "电阻类型:厚膜电阻;阻值:180Ω;精度:±1%;功率:100mW;最大工作电压:75V;温度系数:±100ppm/℃;")
      (fields
        (field (name "Manufacturer Part") "0603WAF1800T5E")
        (field (name "Manufacturer") "UNI-ROYAL(厚声)")
      )
      (libsource (lib "easyedapro") (part "0603WAF1800T5E"))
    )
    (comp (ref "R9")
      (value "180Ω")
      (footprint "easyedapro:R0603")
      (description "电阻类型:厚膜电阻;阻值:180Ω;精度:±1%;功率:100mW;最大工作电压:75V;温度系数:±100ppm/℃;")
      (fields
        (field (name "Manufacturer Part") "0603WAF1800T5E")
        (field (name "Manufacturer") "UNI-ROYAL(厚声)")
      )
      (libsource (lib "easyedapro") (part "0603WAF1800T5E"))
    )
    (comp (ref "R10")
      (value "180Ω")
      (footprint "easyedapro:R0603")
      (description "电阻类型:厚膜电阻;阻值:180Ω;精度:±1%;功率:100mW;最大工作电压:75V;温度系数:±100ppm/℃;")
      (fields
        (field (name "Manufacturer Part") "0603WAF1800T5E")
        (field (name "Manufacturer") "UNI-ROYAL(厚声)")
      )
      (libsource (lib "easyedapro") (part "0603WAF1800T5E"))
    )
    (comp (ref "R11")
      (value "180Ω")
      (footprint "easyedapro:R0603")
      (description "电阻类型:厚膜电阻;阻值:180Ω;精度:±1%;功率:100mW;最大工作电压:75V;温度系数:±100ppm/℃;")
      (fields
        (field (name "Manufacturer Part") "0603WAF1800T5E")
        (field (name "Manufacturer") "UNI-ROYAL(厚声)")
      )
      (libsource (lib "easyedapro") (part "0603WAF1800T5E"))
    )
    (comp (ref "R12")
      (value "180Ω")
      (footprint "easyedapro:R0603")
      (description "电阻类型:厚膜电阻;阻值:180Ω;精度:±1%;功率:100mW;最大工作电压:75V;温度系数:±100ppm/℃;")
      (fields
        (field (name "Manufacturer Part") "0603WAF1800T5E")
        (field (name "Manufacturer") "UNI-ROYAL(厚声)")
      )
      (libsource (lib "easyedapro") (part "0603WAF1800T5E"))
    )
    (comp (ref "R13")
      (value "180Ω")
      (footprint "easyedapro:R0603")
      (description "电阻类型:厚膜电阻;阻值:180Ω;精度:±1%;功率:100mW;最大工作电压:75V;温度系数:±100ppm/℃;")
      (fields
        (field (name "Manufacturer Part") "0603WAF1800T5E")
        (field (name "Manufacturer") "UNI-ROYAL(厚声)")
      )
      (libsource (lib "easyedapro") (part "0603WAF1800T5E"))
    )
    (comp (ref "R14")
      (value "180Ω")
      (footprint "easyedapro:R0603")
      (description "电阻类型:厚膜电阻;阻值:180Ω;精度:±1%;功率:100mW;最大工作电压:75V;温度系数:±100ppm/℃;")
      (fields
        (field (name "Manufacturer Part") "0603WAF1800T5E")
        (field (name "Manufacturer") "UNI-ROYAL(厚声)")
      )
      (libsource (lib "easyedapro") (part "0603WAF1800T5E"))
    )
    (comp (ref "R15")
      (value "180Ω")
      (footprint "easyedapro:R0603")
      (description "电阻类型:厚膜电阻;阻值:180Ω;精度:±1%;功率:100mW;最大工作电压:75V;温度系数:±100ppm/℃;")
      (fields
        (field (name "Manufacturer Part") "0603WAF1800T5E")
        (field (name "Manufacturer") "UNI-ROYAL(厚声)")
      )
      (libsource (lib "easyedapro") (part "0603WAF1800T5E"))
    )
    (comp (ref "R16")
      (value "180Ω")
      (footprint "easyedapro:R0603")
      (description "电阻类型:厚膜电阻;阻值:180Ω;精度:±1%;功率:100mW;最大工作电压:75V;温度系数:±100ppm/℃;")
      (fields
        (field (name "Manufacturer Part") "0603WAF1800T5E")
        (field (name "Manufacturer") "UNI-ROYAL(厚声)")
      )
      (libsource (lib "easyedapro") (part "0603WAF1800T5E"))
    )
    (comp (ref "R17")
      (value "180Ω")
      (footprint "easyedapro:R0603")
      (description "电阻类型:厚膜电阻;阻值:180Ω;精度:±1%;功率:100mW;最大工作电压:75V;温度系数:±100ppm/℃;")
      (fields
        (field (name "Manufacturer Part") "0603WAF1800T5E")
        (field (name "Manufacturer") "UNI-ROYAL(厚声)")
      )
      (libsource (lib "easyedapro") (part "0603WAF1800T5E"))
    )
    (comp (ref "R18")
      (value "180Ω")
      (footprint "easyedapro:R0603")
      (description "电阻类型:厚膜电阻;阻值:180Ω;精度:±1%;功率:100mW;最大工作电压:75V;温度系数:±100ppm/℃;")
      (fields
        (field (name "Manufacturer Part") "0603WAF1800T5E")
        (field (name "Manufacturer") "UNI-ROYAL(厚声)")
      )
      (libsource (lib "easyedapro") (part "0603WAF1800T5E"))
    )
    (comp (ref "R19")
      (value "180Ω")
      (footprint "easyedapro:R0603")
      (description "电阻类型:厚膜电阻;阻值:180Ω;精度:±1%;功率:100mW;最大工作电压:75V;温度系数:±100ppm/℃;")
      (fields
        (field (name "Manufacturer Part") "0603WAF1800T5E")
        (field (name "Manufacturer") "UNI-ROYAL(厚声)")
      )
      (libsource (lib "easyedapro") (part "0603WAF1800T5E"))
    )
    (comp (ref "R20")
      (value "180Ω")
      (footprint "easyedapro:R0603")
      (description "电阻类型:厚膜电阻;阻值:180Ω;精度:±1%;功率:100mW;最大工作电压:75V;温度系数:±100ppm/℃;")
      (fields
        (field (name "Manufacturer Part") "0603WAF1800T5E")
        (field (name "Manufacturer") "UNI-ROYAL(厚声)")
      )
      (libsource (lib "easyedapro") (part "0603WAF1800T5E"))
    )
    (comp (ref "R21")
      (value "180Ω")
      (footprint "easyedapro:R0603")
      (description "电阻类型:厚膜电阻;阻值:180Ω;精度:±1%;功率:100mW;最大工作电压:75V;温度系数:±100ppm/℃;")
      (fields
        (field (name "Manufacturer Part") "0603WAF1800T5E")
        (field (name "Manufacturer") "UNI-ROYAL(厚声)")
      )
      (libsource (lib "easyedapro") (part "0603WAF1800T5E"))
    )
    (comp (ref "R22")
      (value "180Ω")
      (footprint "easyedapro:R0603")
      (description "电阻类型:厚膜电阻;阻值:180Ω;精度:±1%;功率:100mW;最大工作电压:75V;温度系数:±100ppm/℃;")
      (fields
        (field (name "Manufacturer Part") "0603WAF1800T5E")
        (field (name "Manufacturer") "UNI-ROYAL(厚声)")
      )
      (libsource (lib "easyedapro") (part "0603WAF1800T5E"))
    )
    (comp (ref "R23")
      (value "180Ω")
      (footprint "easyedapro:R0603")
      (description "电阻类型:厚膜电阻;阻值:180Ω;精度:±1%;功率:100mW;最大工作电压:75V;温度系数:±100ppm/℃;")
      (fields
        (field (name "Manufacturer Part") "0603WAF1800T5E")
        (field (name "Manufacturer") "UNI-ROYAL(厚声)")
      )
      (libsource (lib "easyedapro") (part "0603WAF1800T5E"))
    )
    (comp (ref "R24")
      (value "180Ω")
      (footprint "easyedapro:R0603")
      (description "电阻类型:厚膜电阻;阻值:180Ω;精度:±1%;功率:100mW;最大工作电压:75V;温度系数:±100ppm/℃;")
      (fields
        (field (name "Manufacturer Part") "0603WAF1800T5E")
        (field (name "Manufacturer") "UNI-ROYAL(厚声)")
      )
      (libsource (lib "easyedapro") (part "0603WAF1800T5E"))
    )
    (comp (ref "R25")
      (value "180Ω")
      (footprint "easyedapro:R0603")
      (description "电阻类型:厚膜电阻;阻值:180Ω;精度:±1%;功率:100mW;最大工作电压:75V;温度系数:±100ppm/℃;")
      (fields
        (field (name "Manufacturer Part") "0603WAF1800T5E")
        (field (name "Manufacturer") "UNI-ROYAL(厚声)")
      )
      (libsource (lib "easyedapro") (part "0603WAF1800T5E"))
    )
    (comp (ref "R26")
      (value "180Ω")
      (footprint "easyedapro:R0603")
      (description "电阻类型:厚膜电阻;阻值:180Ω;精度:±1%;功率:100mW;最大工作电压:75V;温度系数:±100ppm/℃;")
      (fields
        (field (name "Manufacturer Part") "0603WAF1800T5E")
        (field (name "Manufacturer") "UNI-ROYAL(厚声)")
      )
      (libsource (lib "easyedapro") (part "0603WAF1800T5E"))
    )
    (comp (ref "R27")
      (value "180Ω")
      (footprint "easyedapro:R0603")
      (description "电阻类型:厚膜电阻;阻值:180Ω;精度:±1%;功率:100mW;最大工作电压:75V;温度系数:±100ppm/℃;")
      (fields
        (field (name "Manufacturer Part") "0603WAF1800T5E")
        (field (name "Manufacturer") "UNI-ROYAL(厚声)")
      )
      (libsource (lib "easyedapro") (part "0603WAF1800T5E"))
    )
    (comp (ref "R28")
      (value "180Ω")
      (footprint "easyedapro:R0603")
      (description "电阻类型:厚膜电阻;阻值:180Ω;精度:±1%;功率:100mW;最大工作电压:75V;温度系数:±100ppm/℃;")
      (fields
        (field (name "Manufacturer Part") "0603WAF1800T5E")
        (field (name "Manufacturer") "UNI-ROYAL(厚声)")
      )
      (libsource (lib "easyedapro") (part "0603WAF1800T5E"))
    )
    (comp (ref "R29")
      (value "180Ω")
      (footprint "easyedapro:R0603")
      (description "电阻类型:厚膜电阻;阻值:180Ω;精度:±1%;功率:100mW;最大工作电压:75V;温度系数:±100ppm/℃;")
      (fields
        (field (name "Manufacturer Part") "0603WAF1800T5E")
        (field (name "Manufacturer") "UNI-ROYAL(厚声)")
      )
      (libsource (lib "easyedapro") (part "0603WAF1800T5E"))
    )
    (comp (ref "R30")
      (value "180Ω")
      (footprint "easyedapro:R0603")
      (description "电阻类型:厚膜电阻;阻值:180Ω;精度:±1%;功率:100mW;最大工作电压:75V;温度系数:±100ppm/℃;")
      (fields
        (field (name "Manufacturer Part") "0603WAF1800T5E")
        (field (name "Manufacturer") "UNI-ROYAL(厚声)")
      )
      (libsource (lib "easyedapro") (part "0603WAF1800T5E"))
    )
    (comp (ref "R31")
      (value "180Ω")
      (footprint "easyedapro:R0603")
      (description "电阻类型:厚膜电阻;阻值:180Ω;精度:±1%;功率:100mW;最大工作电压:75V;温度系数:±100ppm/℃;")
      (fields
        (field (name "Manufacturer Part") "0603WAF1800T5E")
        (field (name "Manufacturer") "UNI-ROYAL(厚声)")
      )
      (libsource (lib "easyedapro") (part "0603WAF1800T5E"))
    )
    (comp (ref "R32")
      (value "180Ω")
      (footprint "easyedapro:R0603")
      (description "电阻类型:厚膜电阻;阻值:180Ω;精度:±1%;功率:100mW;最大工作电压:75V;温度系数:±100ppm/℃;")
      (fields
        (field (name "Manufacturer Part") "0603WAF1800T5E")
        (field (name "Manufacturer") "UNI-ROYAL(厚声)")
      )
      (libsource (lib "easyedapro") (part "0603WAF1800T5E"))
    )
    (comp (ref "R33")
      (value "180Ω")
      (footprint "easyedapro:R0603")
      (description "电阻类型:厚膜电阻;阻值:180Ω;精度:±1%;功率:100mW;最大工作电压:75V;温度系数:±100ppm/℃;")
      (fields
        (field (name "Manufacturer Part") "0603WAF1800T5E")
        (field (name "Manufacturer") "UNI-ROYAL(厚声)")
      )
      (libsource (lib "easyedapro") (part "0603WAF1800T5E"))
    )
    (comp (ref "R34")
      (value "180Ω")
      (footprint "easyedapro:R0603")
      (description "电阻类型:厚膜电阻;阻值:180Ω;精度:±1%;功率:100mW;最大工作电压:75V;温度系数:±100ppm/℃;")
      (fields
        (field (name "Manufacturer Part") "0603WAF1800T5E")
        (field (name "Manufacturer") "UNI-ROYAL(厚声)")
      )
      (libsource (lib "easyedapro") (part "0603WAF1800T5E"))
    )
    (comp (ref "R35")
      (value "180Ω")
      (footprint "easyedapro:R0603")
      (description "电阻类型:厚膜电阻;阻值:180Ω;精度:±1%;功率:100mW;最大工作电压:75V;温度系数:±100ppm/℃;")
      (fields
        (field (name "Manufacturer Part") "0603WAF1800T5E")
        (field (name "Manufacturer") "UNI-ROYAL(厚声)")
      )
      (libsource (lib "easyedapro") (part "0603WAF1800T5E"))
    )
    (comp (ref "R36")
      (value "180Ω")
      (footprint "easyedapro:R0603")
      (description "电阻类型:厚膜电阻;阻值:180Ω;精度:±1%;功率:100mW;最大工作电压:75V;温度系数:±100ppm/℃;")
      (fields
        (field (name "Manufacturer Part") "0603WAF1800T5E")
        (field (name "Manufacturer") "UNI-ROYAL(厚声)")
      )
      (libsource (lib "easyedapro") (part "0603WAF1800T5E"))
    )
    (comp (ref "R37")
      (value "180Ω")
      (footprint "easyedapro:R0603")
      (description "电阻类型:厚膜电阻;阻值:180Ω;精度:±1%;功率:100mW;最大工作电压:75V;温度系数:±100ppm/℃;")
      (fields
        (field (name "Manufacturer Part") "0603WAF1800T5E")
        (field (name "Manufacturer") "UNI-ROYAL(厚声)")
      )
      (libsource (lib "easyedapro") (part "0603WAF1800T5E"))
    )
    (comp (ref "R38")
      (value "180Ω")
      (footprint "easyedapro:R0603")
      (description "电阻类型:厚膜电阻;阻值:180Ω;精度:±1%;功率:100mW;最大工作电压:75V;温度系数:±100ppm/℃;")
      (fields
        (field (name "Manufacturer Part") "0603WAF1800T5E")
        (field (name "Manufacturer") "UNI-ROYAL(厚声)")
      )
      (libsource (lib "easyedapro") (part "0603WAF1800T5E"))
    )
    (comp (ref "R39")
      (value "180Ω")
      (footprint "easyedapro:R0603")
      (description "电阻类型:厚膜电阻;阻值:180Ω;精度:±1%;功率:100mW;最大工作电压:75V;温度系数:±100ppm/℃;")
      (fields
        (field (name "Manufacturer Part") "0603WAF1800T5E")
        (field (name "Manufacturer") "UNI-ROYAL(厚声)")
      )
      (libsource (lib "easyedapro") (part "0603WAF1800T5E"))
    )
    (comp (ref "R40")
      (value "180Ω")
      (footprint "easyedapro:R0603")
      (description "电阻类型:厚膜电阻;阻值:180Ω;精度:±1%;功率:100mW;最大工作电压:75V;温度系数:±100ppm/℃;")
      (fields
        (field (name "Manufacturer Part") "0603WAF1800T5E")
        (field (name "Manufacturer") "UNI-ROYAL(厚声)")
      )
      (libsource (lib "easyedapro") (part "0603WAF1800T5E"))
    )
  )
  (nets
    (net (code "1") (name "BAT+") (class "Default")
      (node (ref "C2") (pin "1") (pinfunction "1_1") (pintype "input"))
      (node (ref "L1") (pin "1") (pinfunction "1_1") (pintype "unspecified"))
      (node (ref "Q2") (pin "5") (pinfunction "D2_5") (pintype "unspecified"))
      (node (ref "Q2") (pin "6") (pinfunction "D2_6") (pintype "unspecified"))
      (node (ref "R42") (pin "1") (pinfunction "1_1") (pintype "input"))
    )
    (net (code "2") (name "CC1") (class "Default")
      (node (ref "D4") (pin "2") (pinfunction "C_2") (pintype "unspecified"))
      (node (ref "R53") (pin "1") (pinfunction "1_1") (pintype "input"))
      (node (ref "USB1") (pin "A5") (pinfunction "CC1_A5") (pintype "unspecified"))
    )
    (net (code "3") (name "CC2") (class "Default")
      (node (ref "D4") (pin "1") (pinfunction "C_1") (pintype "unspecified"))
      (node (ref "R54") (pin "1") (pinfunction "1_1") (pintype "input"))
      (node (ref "USB1") (pin "B5") (pinfunction "CC2_B5") (pintype "unspecified"))
    )
    (net (code "4") (name "CELL+") (class "Default")
      (node (ref "BT1") (pin "1") (pinfunction "1_1") (pintype "input"))
      (node (ref "Q2") (pin "7") (pinfunction "D1_7") (pintype "unspecified"))
      (node (ref "Q2") (pin "8") (pinfunction "D1_8") (pintype "unspecified"))
      (node (ref "R50") (pin "1") (pinfunction "1_1") (pintype "input"))
      (node (ref "R52") (pin "2") (pinfunction "2_2") (pintype "input"))
    )
    (net (code "5") (name "CELL-") (class "Default")
      (node (ref "BT1") (pin "2") (pinfunction "2_2") (pintype "input"))
      (node (ref "C13") (pin "2") (pinfunction "2_2") (pintype "unspecified"))
      (node (ref "D2") (pin "2") (pinfunction "A_2") (pintype "unspecified"))
      (node (ref "Q3") (pin "2") (pinfunction "E_2") (pintype "unspecified"))
      (node (ref "R49") (pin "1") (pinfunction "1_1") (pintype "input"))
      (node (ref "U3") (pin "5") (pinfunction "GND_5") (pintype "unspecified"))
      (node (ref "U3") (pin "7") (pinfunction "GND_7") (pintype "unspecified"))
      (node (ref "U3") (pin "8") (pinfunction "GND_8") (pintype "unspecified"))
      (node (ref "U3") (pin "9") (pinfunction "EP_9") (pintype "unspecified"))
    )
    (net (code "6") (name "GND") (class "Default")
      (node (ref "C1") (pin "2") (pinfunction "2_2") (pintype "input"))
      (node (ref "C10") (pin "1") (pinfunction "1_1") (pintype "input"))
      (node (ref "C11") (pin "2") (pinfunction "2_2") (pintype "input"))
      (node (ref "C12") (pin "2") (pinfunction "2_2") (pintype "unspecified"))
      (node (ref "C14") (pin "1") (pinfunction "1_1") (pintype "input"))
      (node (ref "C15") (pin "2") (pinfunction "2_2") (pintype "input"))
      (node (ref "C16") (pin "2") (pinfunction "2_2") (pintype "unspecified"))
      (node (ref "C2") (pin "2") (pinfunction "2_2") (pintype "input"))
      (node (ref "C3") (pin "1") (pinfunction "1_1") (pintype "input"))
      (node (ref "C4") (pin "1") (pinfunction "1_1") (pintype "input"))
      (node (ref "C5") (pin "1") (pinfunction "1_1") (pintype "input"))
      (node (ref "C6") (pin "1") (pinfunction "1_1") (pintype "input"))
      (node (ref "C7") (pin "2") (pinfunction "2_2") (pintype "unspecified"))
      (node (ref "C8") (pin "2") (pinfunction "2_2") (pintype "unspecified"))
      (node (ref "C9") (pin "2") (pinfunction "2_2") (pintype "input"))
      (node (ref "D3") (pin "2") (pinfunction "A_2") (pintype "unspecified"))
      (node (ref "D4") (pin "3") (pinfunction "A_3") (pintype "unspecified"))
      (node (ref "D5") (pin "2") (pinfunction "A_2") (pintype "unspecified"))
      (node (ref "Q1") (pin "2") (pinfunction "S_2") (pintype "unspecified"))
      (node (ref "R44") (pin "2") (pinfunction "2_2") (pintype "input"))
      (node (ref "R48") (pin "4") (pinfunction "4_4") (pintype "unspecified"))
      (node (ref "R48") (pin "5") (pinfunction "5_5") (pintype "unspecified"))
      (node (ref "R53") (pin "2") (pinfunction "2_2") (pintype "input"))
      (node (ref "R54") (pin "2") (pinfunction "2_2") (pintype "input"))
      (node (ref "SW1") (pin "1") (pinfunction "1_1") (pintype "unspecified"))
      (node (ref "SW2") (pin "3") (pinfunction "3_3") (pintype "unspecified"))
      (node (ref "SW2") (pin "4") (pinfunction "4_4") (pintype "unspecified"))
      (node (ref "SW2") (pin "5") (pinfunction "5_5") (pintype "unspecified"))
      (node (ref "SW2") (pin "6") (pinfunction "6_6") (pintype "unspecified"))
      (node (ref "SW2") (pin "7") (pinfunction "7_7") (pintype "unspecified"))
      (node (ref "U1") (pin "9") (pinfunction "EP_9") (pintype "unspecified"))
      (node (ref "U2") (pin "1") (pinfunction "GND_1") (pintype "unspecified"))
      (node (ref "U3") (pin "1") (pinfunction "VM_1") (pintype "unspecified"))
      (node (ref "U3") (pin "2") (pinfunction "VM_2") (pintype "unspecified"))
      (node (ref "U3") (pin "3") (pinfunction "VM_3") (pintype "unspecified"))
      (node (ref "U3") (pin "4") (pinfunction "VM_4") (pintype "unspecified"))
      (node (ref "USB1") (pin "1") (pinfunction "EH_1") (pintype "unspecified"))
      (node (ref "USB1") (pin "2") (pinfunction "EH_2") (pintype "unspecified"))
      (node (ref "USB1") (pin "3") (pinfunction "EH_3") (pintype "unspecified"))
      (node (ref "USB1") (pin "4") (pinfunction "EH_4") (pintype "unspecified"))
      (node (ref "USB1") (pin "A12") (pinfunction "GND_A12") (pintype "unspecified"))
      (node (ref "USB1") (pin "B12") (pinfunction "GND_B12") (pintype "unspecified"))
      (node (ref "USB2") (pin "4") (pinfunction "GND_4") (pintype "unspecified"))
      (node (ref "USB2") (pin "5") (pinfunction "5_5") (pintype "unspecified"))
      (node (ref "USB2") (pin "6") (pinfunction "6_6") (pintype "unspecified"))
    )
    (net (code "7") (name "LED1") (class "Default")
      (node (ref "LED41") (pin "2") (pinfunction "+_2") (pintype "input"))
      (node (ref "LED42") (pin "1") (pinfunction "-_1") (pintype "input"))
      (node (ref "U1") (pin "2") (pinfunction "LED1_2") (pintype "unspecified"))
    )
    (net (code "8") (name "LED2") (class "Default")
      (node (ref "LED43") (pin "2") (pinfunction "+_2") (pintype "input"))
      (node (ref "LED44") (pin "1") (pinfunction "-_1") (pintype "input"))
      (node (ref "U1") (pin "3") (pinfunction "LED2_3") (pintype "unspecified"))
    )
    (net (code "9") (name "LED3") (class "Default")
      (node (ref "LED41") (pin "1") (pinfunction "-_1") (pintype "input"))
      (node (ref "LED42") (pin "2") (pinfunction "+_2") (pintype "input"))
      (node (ref "LED43") (pin "1") (pinfunction "-_1") (pintype "input"))
      (node (ref "LED44") (pin "2") (pinfunction "+_2") (pintype "input"))
      (node (ref "U1") (pin "4") (pinfunction "LED3_4") (pintype "unspecified"))
    )
    (net (code "10") (name "LED_PWM") (class "Default")
      (node (ref "LED1") (pin "2") (pinfunction "K_2") (pintype "unspecified"))
      (node (ref "LED10") (pin "2") (pinfunction "K_2") (pintype "unspecified"))
      (node (ref "LED11") (pin "2") (pinfunction "K_2") (pintype "unspecified"))
      (node (ref "LED12") (pin "2") (pinfunction "K_2") (pintype "unspecified"))
      (node (ref "LED13") (pin "2") (pinfunction "K_2") (pintype "unspecified"))
      (node (ref "LED14") (pin "2") (pinfunction "K_2") (pintype "unspecified"))
      (node (ref "LED15") (pin "2") (pinfunction "K_2") (pintype "unspecified"))
      (node (ref "LED16") (pin "2") (pinfunction "K_2") (pintype "unspecified"))
      (node (ref "LED17") (pin "2") (pinfunction "K_2") (pintype "unspecified"))
      (node (ref "LED18") (pin "2") (pinfunction "K_2") (pintype "unspecified"))
      (node (ref "LED19") (pin "2") (pinfunction "K_2") (pintype "unspecified"))
      (node (ref "LED2") (pin "2") (pinfunction "K_2") (pintype "unspecified"))
      (node (ref "LED20") (pin "2") (pinfunction "K_2") (pintype "unspecified"))
      (node (ref "LED21") (pin "2") (pinfunction "K_2") (pintype "unspecified"))
      (node (ref "LED22") (pin "2") (pinfunction "K_2") (pintype "unspecified"))
      (node (ref "LED23") (pin "2") (pinfunction "K_2") (pintype "unspecified"))
      (node (ref "LED24") (pin "2") (pinfunction "K_2") (pintype "unspecified"))
      (node (ref "LED25") (pin "2") (pinfunction "K_2") (pintype "unspecified"))
      (node (ref "LED26") (pin "2") (pinfunction "K_2") (pintype "unspecified"))
      (node (ref "LED27") (pin "2") (pinfunction "K_2") (pintype "unspecified"))
      (node (ref "LED28") (pin "2") (pinfunction "K_2") (pintype "unspecified"))
      (node (ref "LED29") (pin "2") (pinfunction "K_2") (pintype "unspecified"))
      (node (ref "LED3") (pin "2") (pinfunction "K_2") (pintype "unspecified"))
      (node (ref "LED30") (pin "2") (pinfunction "K_2") (pintype "unspecified"))
      (node (ref "LED31") (pin "2") (pinfunction "K_2") (pintype "unspecified"))
      (node (ref "LED32") (pin "2") (pinfunction "K_2") (pintype "unspecified"))
      (node (ref "LED33") (pin "2") (pinfunction "K_2") (pintype "unspecified"))
      (node (ref "LED34") (pin "2") (pinfunction "K_2") (pintype "unspecified"))
      (node (ref "LED35") (pin "2") (pinfunction "K_2") (pintype "unspecified"))
      (node (ref "LED36") (pin "2") (pinfunction "K_2") (pintype "unspecified"))
      (node (ref "LED37") (pin "2") (pinfunction "K_2") (pintype "unspecified"))
      (node (ref "LED38") (pin "2") (pinfunction "K_2") (pintype "unspecified"))
      (node (ref "LED39") (pin "2") (pinfunction "K_2") (pintype "unspecified"))
      (node (ref "LED4") (pin "2") (pinfunction "K_2") (pintype "unspecified"))
      (node (ref "LED40") (pin "2") (pinfunction "K_2") (pintype "unspecified"))
      (node (ref "LED5") (pin "2") (pinfunction "K_2") (pintype "unspecified"))
      (node (ref "LED6") (pin "2") (pinfunction "K_2") (pintype "unspecified"))
      (node (ref "LED7") (pin "2") (pinfunction "K_2") (pintype "unspecified"))
      (node (ref "LED8") (pin "2") (pinfunction "K_2") (pintype "unspecified"))
      (node (ref "LED9") (pin "2") (pinfunction "K_2") (pintype "unspecified"))
      (node (ref "Q1") (pin "3") (pinfunction "D_3") (pintype "unspecified"))
    )
    (net (code "11") (name "Net-(C8-Pad1)") (class "Default")
      (node (ref "C8") (pin "1") (pinfunction "1_1") (pintype "unspecified"))
      (node (ref "R43") (pin "2") (pinfunction "2_2") (pintype "input"))
    )
    (net (code "12") (name "Net-(D1-A)") (class "Default")
      (node (ref "D1") (pin "2") (pinfunction "A_2") (pintype "unspecified"))
      (node (ref "R46") (pin "2") (pinfunction "2_2") (pintype "input"))
      (node (ref "R47") (pin "2") (pinfunction "2_2") (pintype "input"))
      (node (ref "U2") (pin "7") (pinfunction "DISCH_7") (pintype "unspecified"))
    )
    (net (code "13") (name "Net-(D2-C)") (class "Default")
      (node (ref "D2") (pin "1") (pinfunction "C_1") (pintype "unspecified"))
      (node (ref "Q3") (pin "1") (pinfunction "B_1") (pintype "unspecified"))
      (node (ref "R49") (pin "2") (pinfunction "2_2") (pintype "input"))
      (node (ref "R50") (pin "2") (pinfunction "2_2") (pintype "input"))
    )
    (net (code "14") (name "Net-(LED1-A)") (class "Default")
      (node (ref "LED1") (pin "1") (pinfunction "A_1") (pintype "unspecified"))
      (node (ref "R1") (pin "2") (pinfunction "2_2") (pintype "input"))
    )
    (net (code "15") (name "Net-(LED2-A)") (class "Default")
      (node (ref "LED2") (pin "1") (pinfunction "A_1") (pintype "unspecified"))
      (node (ref "R2") (pin "2") (pinfunction "2_2") (pintype "input"))
    )
    (net (code "16") (name "Net-(LED3-A)") (class "Default")
      (node (ref "LED3") (pin "1") (pinfunction "A_1") (pintype "unspecified"))
      (node (ref "R3") (pin "2") (pinfunction "2_2") (pintype "input"))
    )
    (net (code "17") (name "Net-(LED4-A)") (class "Default")
      (node (ref "LED4") (pin "1") (pinfunction "A_1") (pintype "unspecified"))
      (node (ref "R4") (pin "2") (pinfunction "2_2") (pintype "input"))
    )
    (net (code "18") (name "Net-(LED5-A)") (class "Default")
      (node (ref "LED5") (pin "1") (pinfunction "A_1") (pintype "unspecified"))
      (node (ref "R5") (pin "2") (pinfunction "2_2") (pintype "input"))
    )
    (net (code "19") (name "Net-(LED6-A)") (class "Default")
      (node (ref "LED6") (pin "1") (pinfunction "A_1") (pintype "unspecified"))
      (node (ref "R6") (pin "2") (pinfunction "2_2") (pintype "input"))
    )
    (net (code "20") (name "Net-(LED7-A)") (class "Default")
      (node (ref "LED7") (pin "1") (pinfunction "A_1") (pintype "unspecified"))
      (node (ref "R7") (pin "2") (pinfunction "2_2") (pintype "input"))
    )
    (net (code "21") (name "Net-(LED8-A)") (class "Default")
      (node (ref "LED8") (pin "1") (pinfunction "A_1") (pintype "unspecified"))
      (node (ref "R8") (pin "2") (pinfunction "2_2") (pintype "input"))
    )
    (net (code "22") (name "Net-(LED9-A)") (class "Default")
      (node (ref "LED9") (pin "1") (pinfunction "A_1") (pintype "unspecified"))
      (node (ref "R9") (pin "2") (pinfunction "2_2") (pintype "input"))
    )
    (net (code "23") (name "Net-(LED10-A)") (class "Default")
      (node (ref "LED10") (pin "1") (pinfunction "A_1") (pintype "unspecified"))
      (node (ref "R10") (pin "2") (pinfunction "2_2") (pintype "input"))
    )
    (net (code "24") (name "Net-(LED11-A)") (class "Default")
      (node (ref "LED11") (pin "1") (pinfunction "A_1") (pintype "unspecified"))
      (node (ref "R11") (pin "2") (pinfunction "2_2") (pintype "input"))
    )
    (net (code "25") (name "Net-(LED12-A)") (class "Default")
      (node (ref "LED12") (pin "1") (pinfunction "A_1") (pintype "unspecified"))
      (node (ref "R12") (pin "2") (pinfunction "2_2") (pintype "input"))
    )
    (net (code "26") (name "Net-(LED13-A)") (class "Default")
      (node (ref "LED13") (pin "1") (pinfunction "A_1") (pintype "unspecified"))
      (node (ref "R13") (pin "2") (pinfunction "2_2") (pintype "input"))
    )
    (net (code "27") (name "Net-(LED14-A)") (class "Default")
      (node (ref "LED14") (pin "1") (pinfunction "A_1") (pintype "unspecified"))
      (node (ref "R14") (pin "2") (pinfunction "2_2") (pintype "input"))
    )
    (net (code "28") (name "Net-(LED15-A)") (class "Default")
      (node (ref "LED15") (pin "1") (pinfunction "A_1") (pintype "unspecified"))
      (node (ref "R15") (pin "2") (pinfunction "2_2") (pintype "input"))
    )
    (net (code "29") (name "Net-(LED16-A)") (class "Default")
      (node (ref "LED16") (pin "1") (pinfunction "A_1") (pintype "unspecified"))
      (node (ref "R16") (pin "2") (pinfunction "2_2") (pintype "input"))
    )
    (net (code "30") (name "Net-(LED17-A)") (class "Default")
      (node (ref "LED17") (pin "1") (pinfunction "A_1") (pintype "unspecified"))
      (node (ref "R17") (pin "2") (pinfunction "2_2") (pintype "input"))
    )
    (net (code "31") (name "Net-(LED18-A)") (class "Default")
      (node (ref "LED18") (pin "1") (pinfunction "A_1") (pintype "unspecified"))
      (node (ref "R18") (pin "2") (pinfunction "2_2") (pintype "input"))
    )
    (net (code "32") (name "Net-(LED19-A)") (class "Default")
      (node (ref "LED19") (pin "1") (pinfunction "A_1") (pintype "unspecified"))
      (node (ref "R19") (pin "2") (pinfunction "2_2") (pintype "input"))
    )
    (net (code "33") (name "Net-(LED20-A)") (class "Default")
      (node (ref "LED20") (pin "1") (pinfunction "A_1") (pintype "unspecified"))
      (node (ref "R20") (pin "2") (pinfunction "2_2") (pintype "input"))
    )
    (net (code "34") (name "Net-(LED21-A)") (class "Default")
      (node (ref "LED21") (pin "1") (pinfunction "A_1") (pintype "unspecified"))
      (node (ref "R21") (pin "2") (pinfunction "2_2") (pintype "input"))
    )
    (net (code "35") (name "Net-(LED22-A)") (class "Default")
      (node (ref "LED22") (pin "1") (pinfunction "A_1") (pintype "unspecified"))
      (node (ref "R22") (pin "2") (pinfunction "2_2") (pintype "input"))
    )
    (net (code "36") (name "Net-(LED23-A)") (class "Default")
      (node (ref "LED23") (pin "1") (pinfunction "A_1") (pintype "unspecified"))
      (node (ref "R23") (pin "2") (pinfunction "2_2") (pintype "input"))
    )
    (net (code "37") (name "Net-(LED24-A)") (class "Default")
      (node (ref "LED24") (pin "1") (pinfunction "A_1") (pintype "unspecified"))
      (node (ref "R24") (pin "2") (pinfunction "2_2") (pintype "input"))
    )
    (net (code "38") (name "Net-(LED25-A)") (class "Default")
      (node (ref "LED25") (pin "1") (pinfunction "A_1") (pintype "unspecified"))
      (node (ref "R25") (pin "2") (pinfunction "2_2") (pintype "input"))
    )
    (net (code "39") (name "Net-(LED26-A)") (class "Default")
      (node (ref "LED26") (pin "1") (pinfunction "A_1") (pintype "unspecified"))
      (node (ref "R26") (pin "2") (pinfunction "2_2") (pintype "input"))
    )
    (net (code "40") (name "Net-(LED27-A)") (class "Default")
      (node (ref "LED27") (pin "1") (pinfunction "A_1") (pintype "unspecified"))
      (node (ref "R27") (pin "2") (pinfunction "2_2") (pintype "input"))
    )
    (net (code "41") (name "Net-(LED28-A)") (class "Default")
      (node (ref "LED28") (pin "1") (pinfunction "A_1") (pintype "unspecified"))
      (node (ref "R28") (pin "2") (pinfunction "2_2") (pintype "input"))
    )
    (net (code "42") (name "Net-(LED29-A)") (class "Default")
      (node (ref "LED29") (pin "1") (pinfunction "A_1") (pintype "unspecified"))
      (node (ref "R29") (pin "2") (pinfunction "2_2") (pintype "input"))
    )
    (net (code "43") (name "Net-(LED30-A)") (class "Default")
      (node (ref "LED30") (pin "1") (pinfunction "A_1") (pintype "unspecified"))
      (node (ref "R30") (pin "2") (pinfunction "2_2") (pintype "input"))
    )
    (net (code "44") (name "Net-(LED31-A)") (class "Default")
      (node (ref "LED31") (pin "1") (pinfunction "A_1") (pintype "unspecified"))
      (node (ref "R31") (pin "2") (pinfunction "2_2") (pintype "input"))
    )
    (net (code "45") (name "Net-(LED32-A)") (class "Default")
      (node (ref "LED32") (pin "1") (pinfunction "A_1") (pintype "unspecified"))
      (node (ref "R32") (pin "2") (pinfunction "2_2") (pintype "input"))
    )
    (net (code "46") (name "Net-(LED33-A)") (class "Default")
      (node (ref "LED33") (pin "1") (pinfunction "A_1") (pintype "unspecified"))
      (node (ref "R33") (pin "2") (pinfunction "2_2") (pintype "input"))
    )
    (net (code "47") (name "Net-(LED34-A)") (class "Default")
      (node (ref "LED34") (pin "1") (pinfunction "A_1") (pintype "unspecified"))
      (node (ref "R34") (pin "2") (pinfunction "2_2") (pintype "input"))
    )
    (net (code "48") (name "Net-(LED35-A)") (class "Default")
      (node (ref "LED35") (pin "1") (pinfunction "A_1") (pintype "unspecified"))
      (node (ref "R35") (pin "2") (pinfunction "2_2") (pintype "input"))
    )
    (net (code "49") (name "Net-(LED36-A)") (class "Default")
      (node (ref "LED36") (pin "1") (pinfunction "A_1") (pintype "unspecified"))
      (node (ref "R36") (pin "2") (pinfunction "2_2") (pintype "input"))
    )
    (net (code "50") (name "Net-(LED37-A)") (class "Default")
      (node (ref "LED37") (pin "1") (pinfunction "A_1") (pintype "unspecified"))
      (node (ref "R37") (pin "2") (pinfunction "2_2") (pintype "input"))
    )
    (net (code "51") (name "Net-(LED38-A)") (class "Default")
      (node (ref "LED38") (pin "1") (pinfunction "A_1") (pintype "unspecified"))
      (node (ref "R38") (pin "2") (pinfunction "2_2") (pintype "input"))
    )
    (net (code "52") (name "Net-(LED39-A)") (class "Default")
      (node (ref "LED39") (pin "1") (pinfunction "A_1") (pintype "unspecified"))
      (node (ref "R39") (pin "2") (pinfunction "2_2") (pintype "input"))
    )
    (net (code "53") (name "Net-(LED40-A)") (class "Default")
      (node (ref "LED40") (pin "1") (pinfunction "A_1") (pintype "unspecified"))
      (node (ref "R40") (pin "2") (pinfunction "2_2") (pintype "input"))
    )
    (net (code "54") (name "Net-(Q1-G)") (class "Default")
      (node (ref "Q1") (pin "1") (pinfunction "G_1") (pintype "unspecified"))
      (node (ref "R44") (pin "1") (pinfunction "1_1") (pintype "input"))
      (node (ref "R45") (pin "1") (pinfunction "1_1") (pintype "input"))
    )
    (net (code "55") (name "Net-(Q2-G1)") (class "Default")
      (node (ref "Q2") (pin "2") (pinfunction "G1_2") (pintype "unspecified"))
      (node (ref "Q2") (pin "4") (pinfunction "G2_4") (pintype "unspecified"))
      (node (ref "Q3") (pin "3") (pinfunction "C_3") (pintype "unspecified"))
      (node (ref "R51") (pin "1") (pinfunction "1_1") (pintype "input"))
    )
    (net (code "56") (name "Net-(Q2-S1)") (class "Default")
      (node (ref "Q2") (pin "1") (pinfunction "S1_1") (pintype "unspecified"))
      (node (ref "Q2") (pin "3") (pinfunction "S2_3") (pintype "unspecified"))
      (node (ref "R51") (pin "2") (pinfunction "2_2") (pintype "input"))
    )
    (net (code "57") (name "Net-(R41-Pad2)") (class "Default")
      (node (ref "R41") (pin "2") (pinfunction "2_2") (pintype "input"))
      (node (ref "SW1") (pin "4") (pinfunction "4_4") (pintype "unspecified"))
    )
    (net (code "58") (name "Net-(R47-Pad1)") (class "Default")
      (node (ref "R47") (pin "1") (pinfunction "1_1") (pintype "input"))
      (node (ref "R48") (pin "3") (pinfunction "3_3") (pintype "unspecified"))
    )
    (net (code "59") (name "Net-(U1-BAT)") (class "Default")
      (node (ref "C1") (pin "1") (pinfunction "1_1") (pintype "input"))
      (node (ref "R42") (pin "2") (pinfunction "2_2") (pintype "input"))
      (node (ref "U1") (pin "6") (pinfunction "BAT_6") (pintype "unspecified"))
    )
    (net (code "60") (name "Net-(U1-KEY)") (class "Default")
      (node (ref "R41") (pin "1") (pinfunction "1_1") (pintype "input"))
      (node (ref "U1") (pin "5") (pinfunction "KEY_5") (pintype "unspecified"))
    )
    (net (code "61") (name "Net-(U1-SW)") (class "Default")
      (node (ref "L1") (pin "2") (pinfunction "2_2") (pintype "unspecified"))
      (node (ref "U1") (pin "7") (pinfunction "SW_7") (pintype "unspecified"))
    )
    (net (code "62") (name "Net-(U2-CONT)") (class "Default")
      (node (ref "C11") (pin "1") (pinfunction "1_1") (pintype "input"))
      (node (ref "U2") (pin "5") (pinfunction "CONT_5") (pintype "unspecified"))
    )
    (net (code "63") (name "Net-(U2-OUT)") (class "Default")
      (node (ref "R45") (pin "2") (pinfunction "2_2") (pintype "input"))
      (node (ref "U2") (pin "3") (pinfunction "OUT_3") (pintype "unspecified"))
    )
    (net (code "64") (name "Net-(U2-RESET)") (class "Default")
      (node (ref "SW2") (pin "2") (pinfunction "2_2") (pintype "unspecified"))
      (node (ref "U2") (pin "4") (pinfunction "RESET_4") (pintype "unspecified"))
    )
    (net (code "65") (name "Net-(U3-VDD)") (class "Default")
      (node (ref "C13") (pin "1") (pinfunction "1_1") (pintype "unspecified"))
      (node (ref "R52") (pin "1") (pinfunction "1_1") (pintype "input"))
      (node (ref "U3") (pin "6") (pinfunction "VDD_6") (pintype "unspecified"))
    )
    (net (code "66") (name "Net-(USB2-D+)") (class "Default")
      (node (ref "USB2") (pin "2") (pinfunction "D-_2") (pintype "unspecified"))
      (node (ref "USB2") (pin "3") (pinfunction "D+_3") (pintype "unspecified"))
    )
    (net (code "67") (name "PWM_CT") (class "Default")
      (node (ref "C12") (pin "1") (pinfunction "1_1") (pintype "unspecified"))
      (node (ref "D1") (pin "1") (pinfunction "C_1") (pintype "unspecified"))
      (node (ref "R48") (pin "1") (pinfunction "1_1") (pintype "unspecified"))
      (node (ref "R48") (pin "2") (pinfunction "2_2") (pintype "unspecified"))
      (node (ref "U2") (pin "2") (pinfunction "TRIG_2") (pintype "unspecified"))
      (node (ref "U2") (pin "6") (pinfunction "THRES_6") (pintype "unspecified"))
    )
    (net (code "68") (name "VIN") (class "Default")
      (node (ref "C7") (pin "1") (pinfunction "1_1") (pintype "unspecified"))
      (node (ref "D3") (pin "1") (pinfunction "K_1") (pintype "unspecified"))
      (node (ref "R43") (pin "1") (pinfunction "1_1") (pintype "input"))
      (node (ref "U1") (pin "1") (pinfunction "VIN_1") (pintype "unspecified"))
      (node (ref "USB1") (pin "A9") (pinfunction "VBUS_A9") (pintype "unspecified"))
      (node (ref "USB1") (pin "B9") (pinfunction "VBUS_B9") (pintype "unspecified"))
    )
    (net (code "69") (name "VOUT") (class "Default")
      (node (ref "C10") (pin "2") (pinfunction "2_2") (pintype "input"))
      (node (ref "C14") (pin "2") (pinfunction "2_2") (pintype "input"))
      (node (ref "C15") (pin "1") (pinfunction "1_1") (pintype "input"))
      (node (ref "C16") (pin "1") (pinfunction "1_1") (pintype "unspecified"))
      (node (ref "C3") (pin "2") (pinfunction "2_2") (pintype "input"))
      (node (ref "C4") (pin "2") (pinfunction "2_2") (pintype "input"))
      (node (ref "C5") (pin "2") (pinfunction "2_2") (pintype "input"))
      (node (ref "C6") (pin "2") (pinfunction "2_2") (pintype "input"))
      (node (ref "C9") (pin "1") (pinfunction "1_1") (pintype "input"))
      (node (ref "D5") (pin "1") (pinfunction "K_1") (pintype "unspecified"))
      (node (ref "R1") (pin "1") (pinfunction "1_1") (pintype "input"))
      (node (ref "R10") (pin "1") (pinfunction "1_1") (pintype "input"))
      (node (ref "R11") (pin "1") (pinfunction "1_1") (pintype "input"))
      (node (ref "R12") (pin "1") (pinfunction "1_1") (pintype "input"))
      (node (ref "R13") (pin "1") (pinfunction "1_1") (pintype "input"))
      (node (ref "R14") (pin "1") (pinfunction "1_1") (pintype "input"))
      (node (ref "R15") (pin "1") (pinfunction "1_1") (pintype "input"))
      (node (ref "R16") (pin "1") (pinfunction "1_1") (pintype "input"))
      (node (ref "R17") (pin "1") (pinfunction "1_1") (pintype "input"))
      (node (ref "R18") (pin "1") (pinfunction "1_1") (pintype "input"))
      (node (ref "R19") (pin "1") (pinfunction "1_1") (pintype "input"))
      (node (ref "R2") (pin "1") (pinfunction "1_1") (pintype "input"))
      (node (ref "R20") (pin "1") (pinfunction "1_1") (pintype "input"))
      (node (ref "R21") (pin "1") (pinfunction "1_1") (pintype "input"))
      (node (ref "R22") (pin "1") (pinfunction "1_1") (pintype "input"))
      (node (ref "R23") (pin "1") (pinfunction "1_1") (pintype "input"))
      (node (ref "R24") (pin "1") (pinfunction "1_1") (pintype "input"))
      (node (ref "R25") (pin "1") (pinfunction "1_1") (pintype "input"))
      (node (ref "R26") (pin "1") (pinfunction "1_1") (pintype "input"))
      (node (ref "R27") (pin "1") (pinfunction "1_1") (pintype "input"))
      (node (ref "R28") (pin "1") (pinfunction "1_1") (pintype "input"))
      (node (ref "R29") (pin "1") (pinfunction "1_1") (pintype "input"))
      (node (ref "R3") (pin "1") (pinfunction "1_1") (pintype "input"))
      (node (ref "R30") (pin "1") (pinfunction "1_1") (pintype "input"))
      (node (ref "R31") (pin "1") (pinfunction "1_1") (pintype "input"))
      (node (ref "R32") (pin "1") (pinfunction "1_1") (pintype "input"))
      (node (ref "R33") (pin "1") (pinfunction "1_1") (pintype "input"))
      (node (ref "R34") (pin "1") (pinfunction "1_1") (pintype "input"))
      (node (ref "R35") (pin "1") (pinfunction "1_1") (pintype "input"))
      (node (ref "R36") (pin "1") (pinfunction "1_1") (pintype "input"))
      (node (ref "R37") (pin "1") (pinfunction "1_1") (pintype "input"))
      (node (ref "R38") (pin "1") (pinfunction "1_1") (pintype "input"))
      (node (ref "R39") (pin "1") (pinfunction "1_1") (pintype "input"))
      (node (ref "R4") (pin "1") (pinfunction "1_1") (pintype "input"))
      (node (ref "R40") (pin "1") (pinfunction "1_1") (pintype "input"))
      (node (ref "R46") (pin "1") (pinfunction "1_1") (pintype "input"))
      (node (ref "R5") (pin "1") (pinfunction "1_1") (pintype "input"))
      (node (ref "R6") (pin "1") (pinfunction "1_1") (pintype "input"))
      (node (ref "R7") (pin "1") (pinfunction "1_1") (pintype "input"))
      (node (ref "R8") (pin "1") (pinfunction "1_1") (pintype "input"))
      (node (ref "R9") (pin "1") (pinfunction "1_1") (pintype "input"))
      (node (ref "SW2") (pin "1") (pinfunction "1_1") (pintype "unspecified"))
      (node (ref "U1") (pin "8") (pinfunction "VOUT_8") (pintype "unspecified"))
      (node (ref "U2") (pin "8") (pinfunction "VDD_8") (pintype "unspecified"))
      (node (ref "USB2") (pin "1") (pinfunction "VCC_1") (pintype "unspecified"))
    )
    (net (code "70") (name "unconnected-(D4-NC-Pad4)") (class "Default")
      (node (ref "D4") (pin "4") (pinfunction "NC_4") (pintype "unspecified+no_connect"))
    )
    (net (code "71") (name "unconnected-(D4-NC-Pad5)") (class "Default")
      (node (ref "D4") (pin "5") (pinfunction "NC_5") (pintype "unspecified+no_connect"))
    )
    (net (code "72") (name "unconnected-(D4-NC-Pad6)") (class "Default")
      (node (ref "D4") (pin "6") (pinfunction "NC_6") (pintype "unspecified+no_connect"))
    )
    (net (code "73") (name "unconnected-(SW1-Pad2)") (class "Default")
      (node (ref "SW1") (pin "2") (pinfunction "2_2") (pintype "unspecified+no_connect"))
    )
    (net (code "74") (name "unconnected-(SW1-Pad3)") (class "Default")
      (node (ref "SW1") (pin "3") (pinfunction "3_3") (pintype "unspecified+no_connect"))
    )
  )
)
